# sensor_004.net
KiCad netlist of a schematic drawn in EAGLE
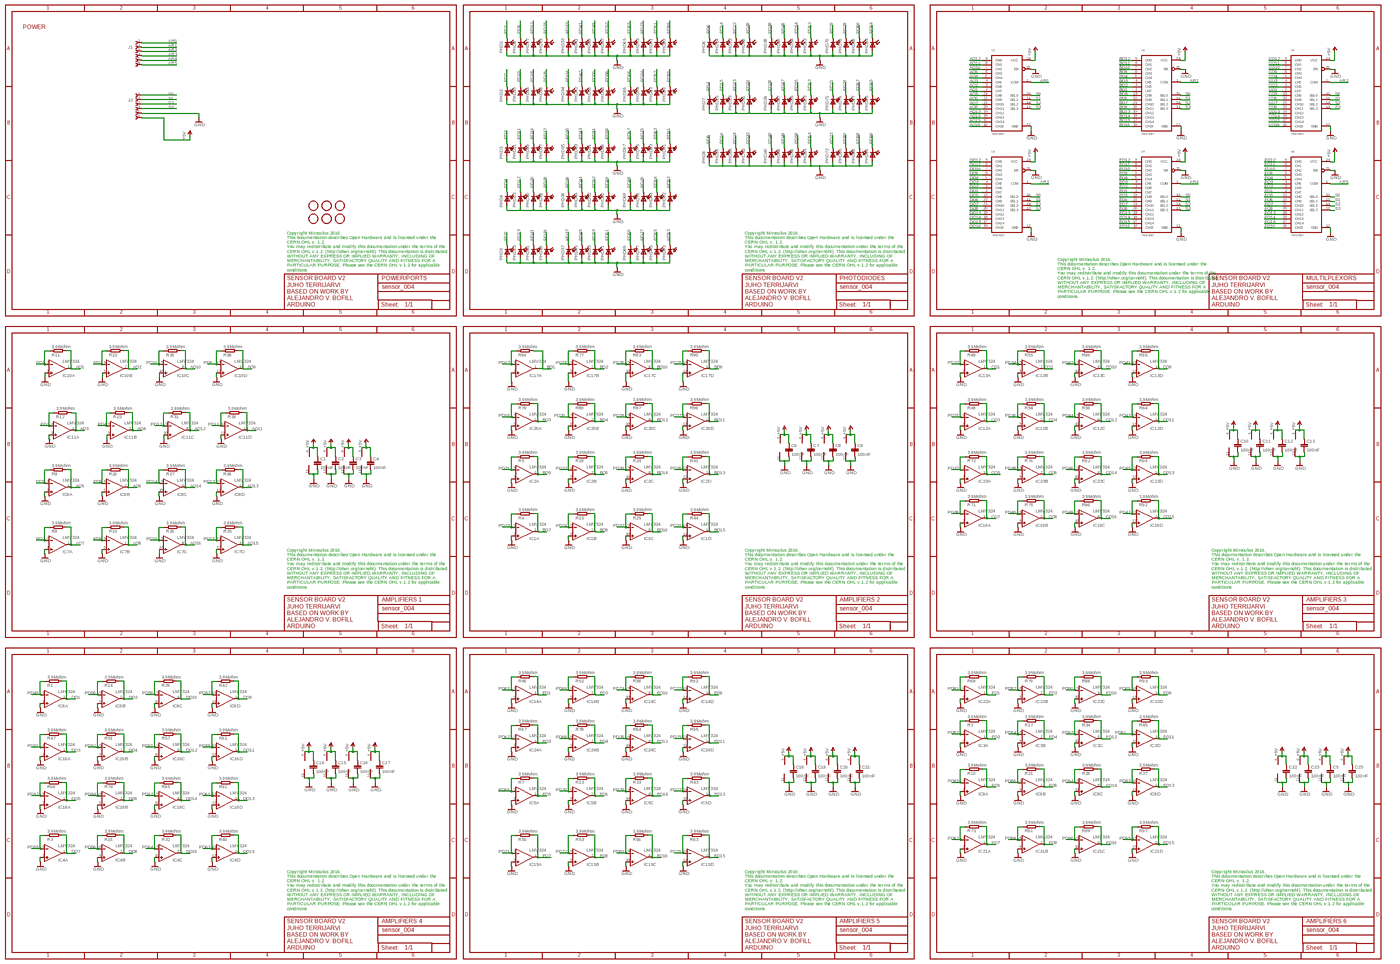
[diagram p0: schematic, sheet 1, overview]
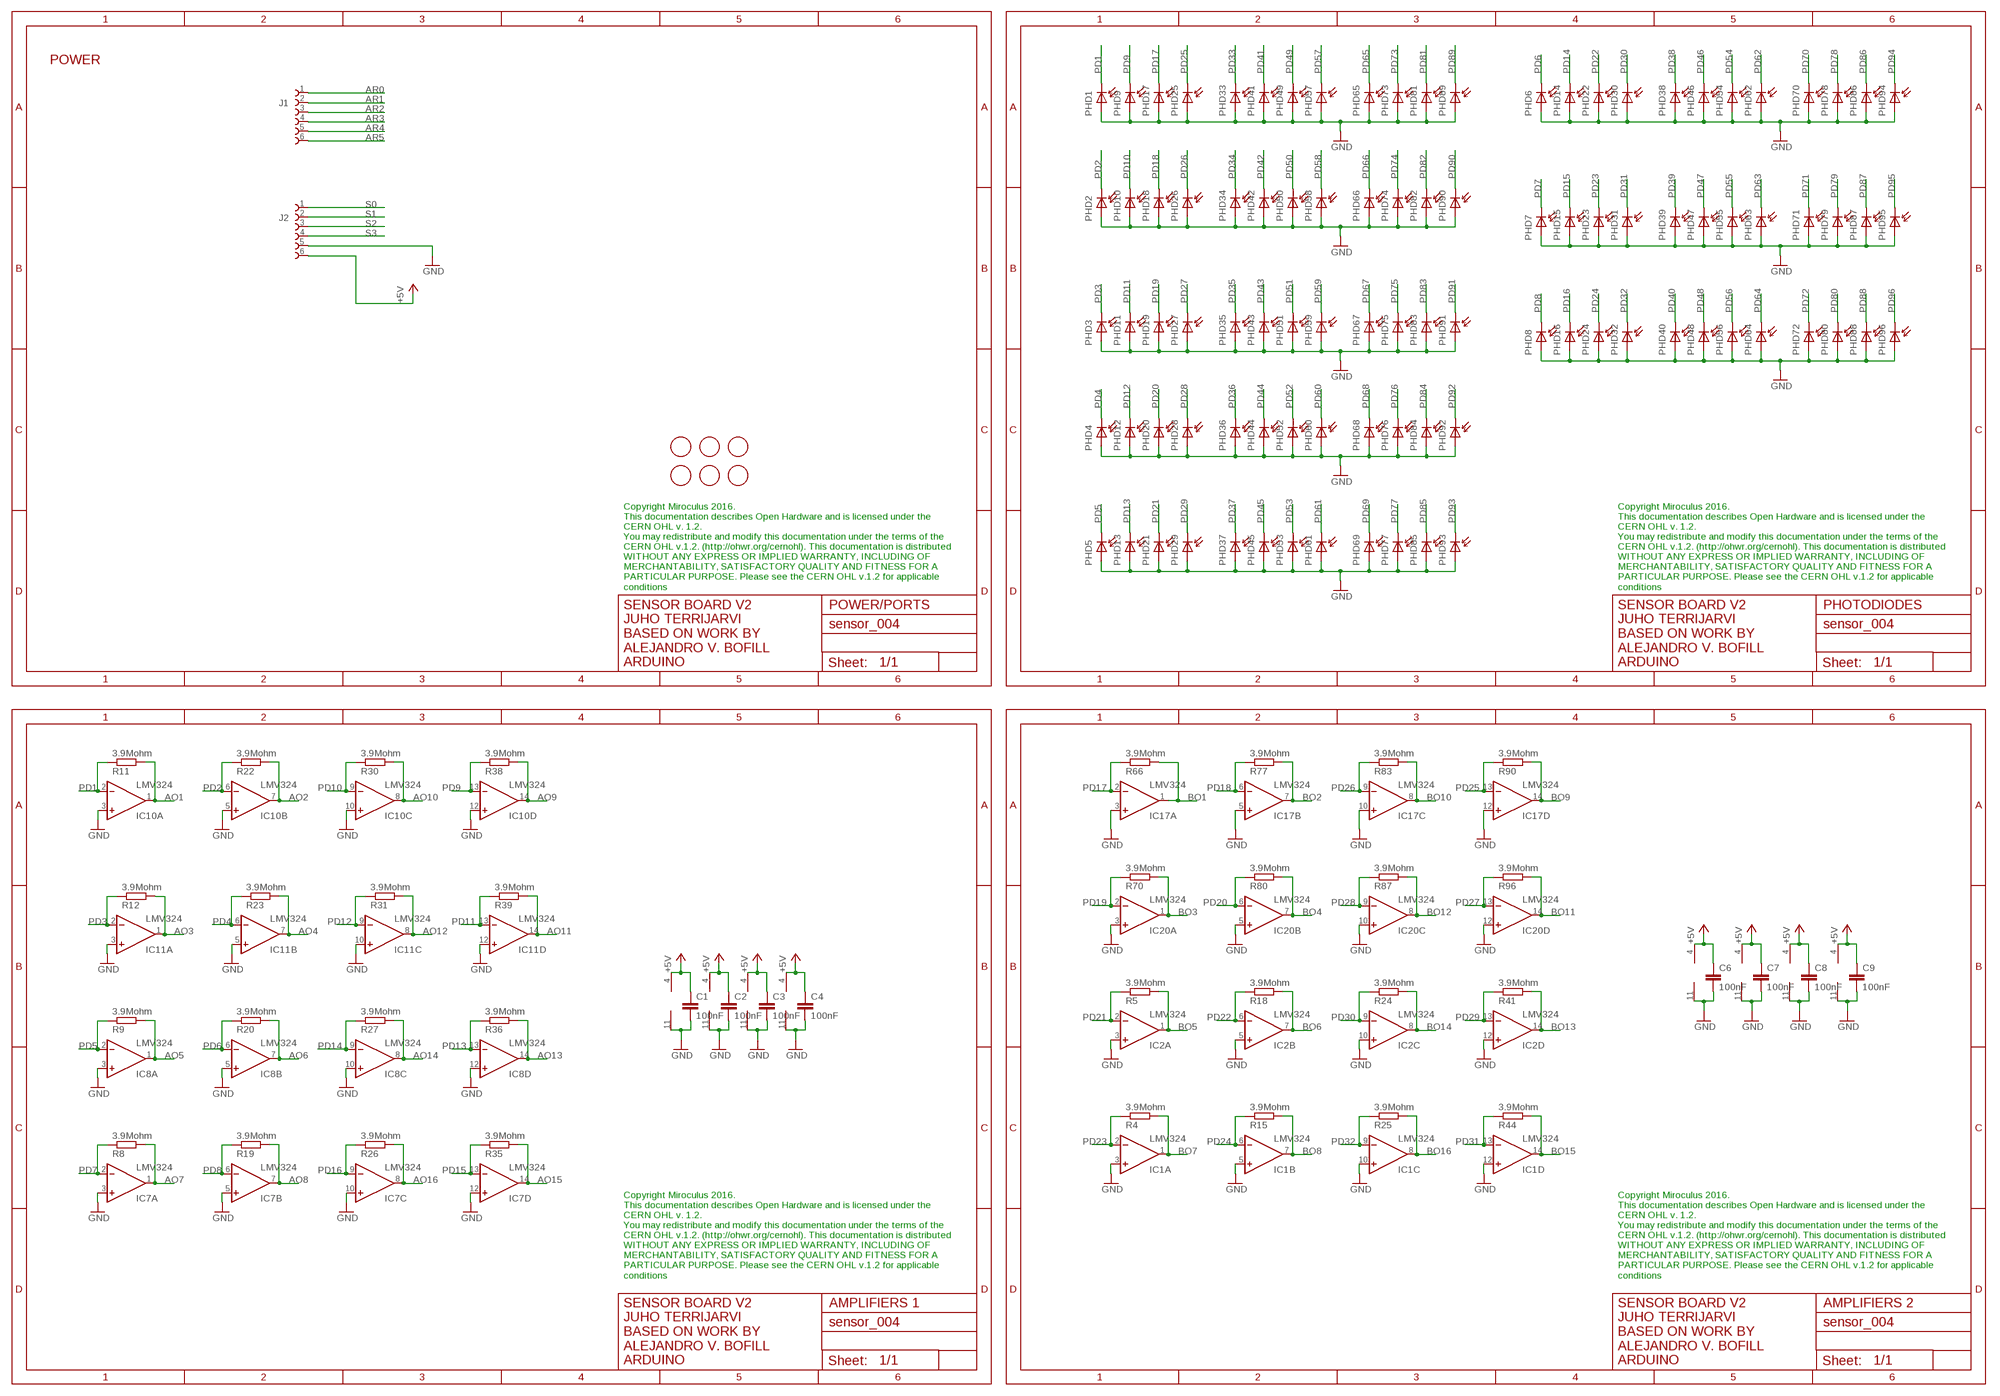
[diagram p1: schematic, sheet 1, part 1 of 4]
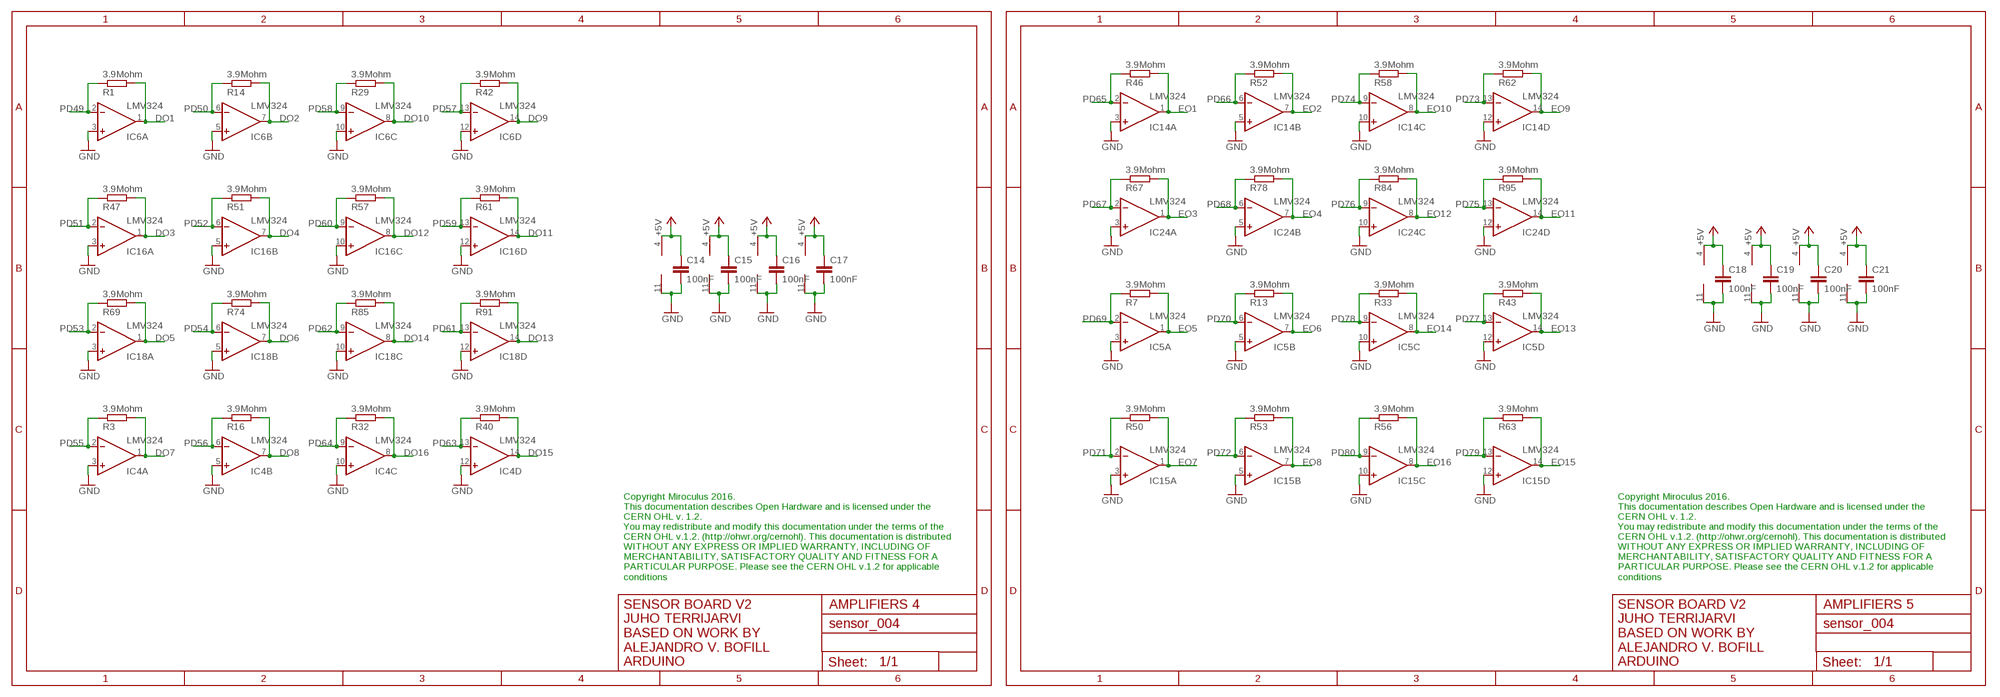
[diagram p2: schematic, sheet 1, part 2 of 4]
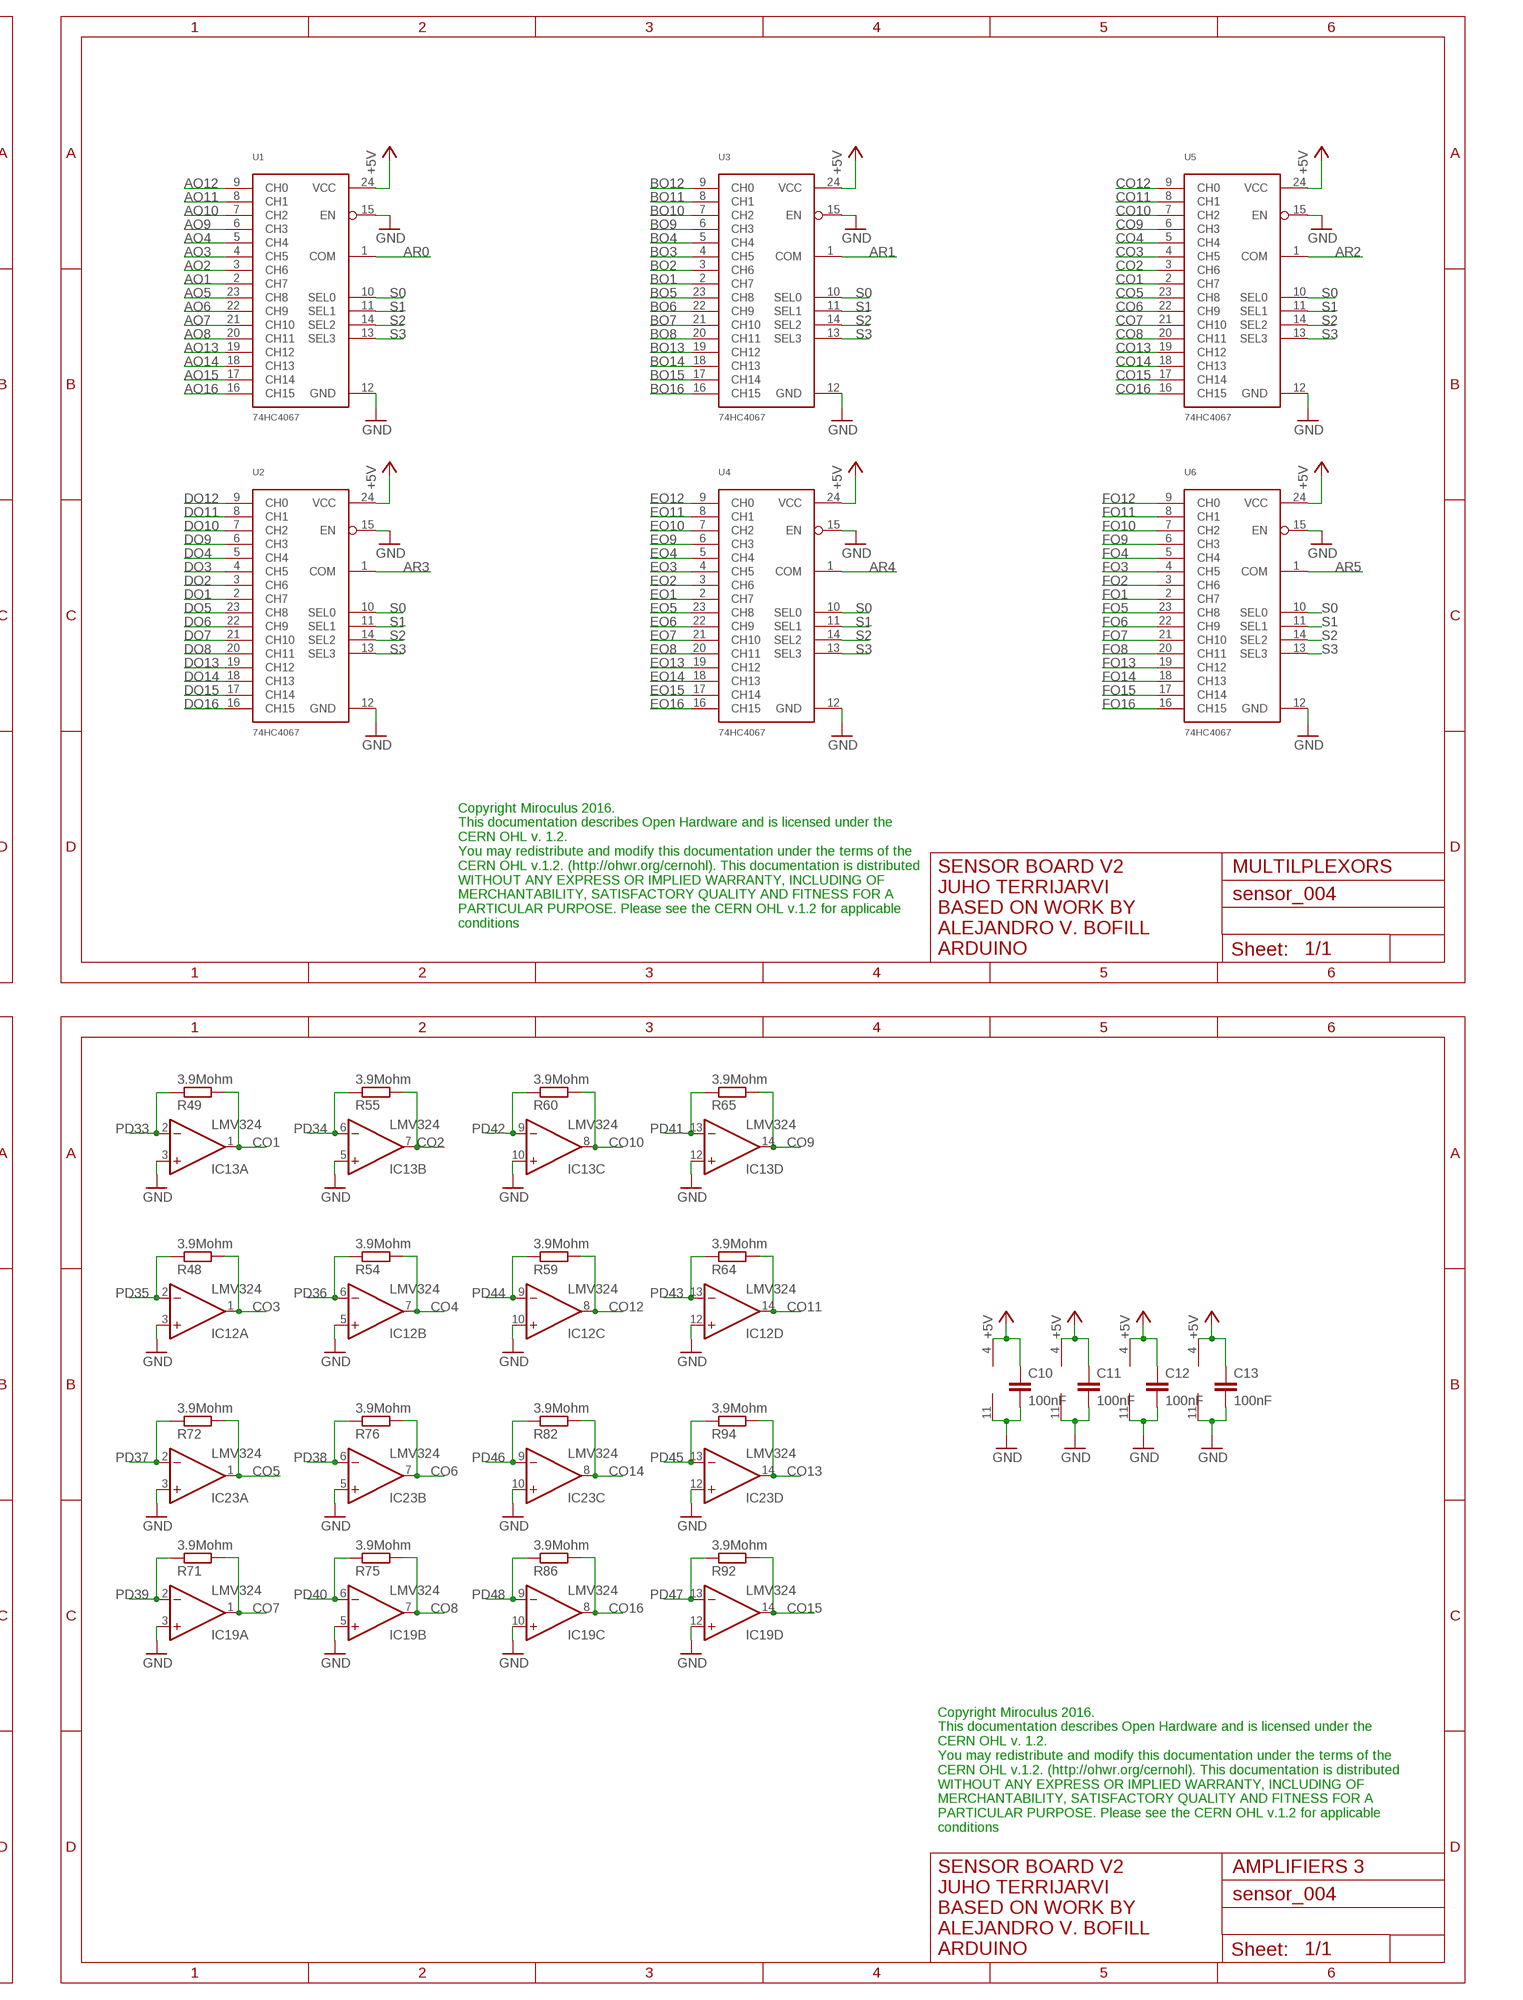
[diagram p3: schematic, sheet 1, part 3 of 4]
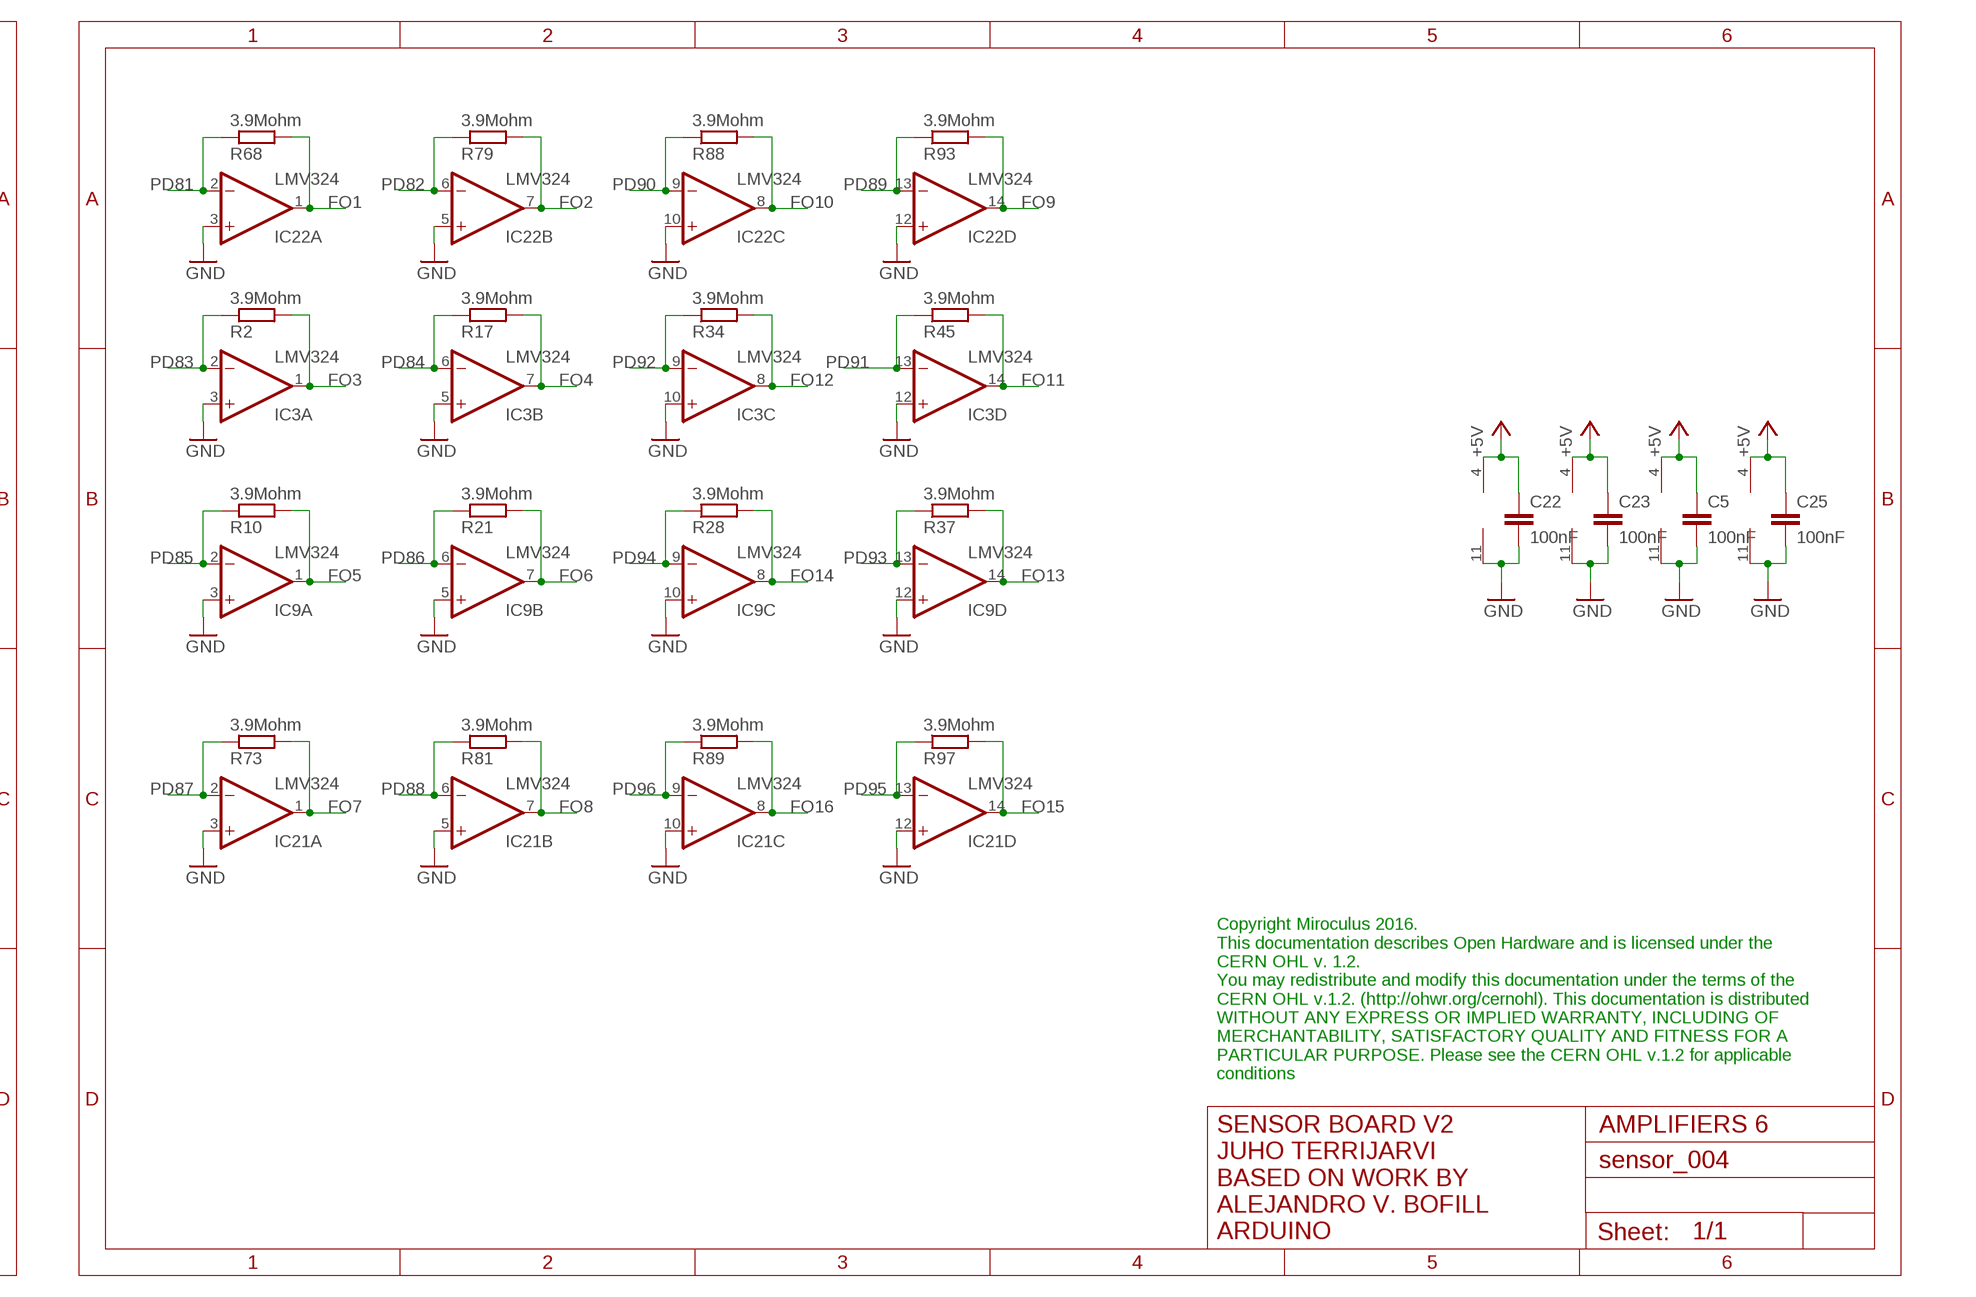
[diagram p4: schematic, sheet 1, part 4 of 4]

(export (version "E")
  (design (tool "Eeschema 10.0.6"))
  (components
    (comp (ref "C1")
      (value "100nF")
      (footprint "eagle-import:C0603")
      (libsource (lib "eagle-import") (part "C-EUC0603"))
    )
    (comp (ref "C2")
      (value "100nF")
      (footprint "eagle-import:C0603")
      (libsource (lib "eagle-import") (part "C-EUC0603"))
    )
    (comp (ref "C3")
      (value "100nF")
      (footprint "eagle-import:C0603")
      (libsource (lib "eagle-import") (part "C-EUC0603"))
    )
    (comp (ref "C4")
      (value "100nF")
      (footprint "eagle-import:C0603")
      (libsource (lib "eagle-import") (part "C-EUC0603"))
    )
    (comp (ref "C5")
      (value "100nF")
      (footprint "eagle-import:C0603")
      (libsource (lib "eagle-import") (part "C-EUC0603"))
    )
    (comp (ref "C6")
      (value "100nF")
      (footprint "eagle-import:C0603")
      (libsource (lib "eagle-import") (part "C-EUC0603"))
    )
    (comp (ref "C7")
      (value "100nF")
      (footprint "eagle-import:C0603")
      (libsource (lib "eagle-import") (part "C-EUC0603"))
    )
    (comp (ref "C8")
      (value "100nF")
      (footprint "eagle-import:C0603")
      (libsource (lib "eagle-import") (part "C-EUC0603"))
    )
    (comp (ref "C9")
      (value "100nF")
      (footprint "eagle-import:C0603")
      (libsource (lib "eagle-import") (part "C-EUC0603"))
    )
    (comp (ref "C10")
      (value "100nF")
      (footprint "eagle-import:C0603")
      (libsource (lib "eagle-import") (part "C-EUC0603"))
    )
    (comp (ref "C11")
      (value "100nF")
      (footprint "eagle-import:C0603")
      (libsource (lib "eagle-import") (part "C-EUC0603"))
    )
    (comp (ref "C12")
      (value "100nF")
      (footprint "eagle-import:C0603")
      (libsource (lib "eagle-import") (part "C-EUC0603"))
    )
    (comp (ref "C13")
      (value "100nF")
      (footprint "eagle-import:C0603")
      (libsource (lib "eagle-import") (part "C-EUC0603"))
    )
    (comp (ref "C14")
      (value "100nF")
      (footprint "eagle-import:C0603")
      (libsource (lib "eagle-import") (part "C-EUC0603"))
    )
    (comp (ref "C15")
      (value "100nF")
      (footprint "eagle-import:C0603")
      (libsource (lib "eagle-import") (part "C-EUC0603"))
    )
    (comp (ref "C16")
      (value "100nF")
      (footprint "eagle-import:C0603")
      (libsource (lib "eagle-import") (part "C-EUC0603"))
    )
    (comp (ref "C17")
      (value "100nF")
      (footprint "eagle-import:C0603")
      (libsource (lib "eagle-import") (part "C-EUC0603"))
    )
    (comp (ref "C18")
      (value "100nF")
      (footprint "eagle-import:C0603")
      (libsource (lib "eagle-import") (part "C-EUC0603"))
    )
    (comp (ref "C19")
      (value "100nF")
      (footprint "eagle-import:C0603")
      (libsource (lib "eagle-import") (part "C-EUC0603"))
    )
    (comp (ref "C20")
      (value "100nF")
      (footprint "eagle-import:C0603")
      (libsource (lib "eagle-import") (part "C-EUC0603"))
    )
    (comp (ref "C21")
      (value "100nF")
      (footprint "eagle-import:C0603")
      (libsource (lib "eagle-import") (part "C-EUC0603"))
    )
    (comp (ref "C22")
      (value "100nF")
      (footprint "eagle-import:C0603")
      (libsource (lib "eagle-import") (part "C-EUC0603"))
    )
    (comp (ref "C23")
      (value "100nF")
      (footprint "eagle-import:C0603")
      (libsource (lib "eagle-import") (part "C-EUC0603"))
    )
    (comp (ref "C25")
      (value "100nF")
      (footprint "eagle-import:C0603")
      (libsource (lib "eagle-import") (part "C-EUC0603"))
    )
    (comp (ref "FD1")
      (value "FIDUCIALMOUNT")
      (footprint "eagle-import:FIDUCIA-MOUNT")
      (libsource (lib "eagle-import") (part "FIDUCIALMOUNT"))
    )
    (comp (ref "FD2")
      (value "FIDUCIALMOUNT")
      (footprint "eagle-import:FIDUCIA-MOUNT")
      (libsource (lib "eagle-import") (part "FIDUCIALMOUNT"))
    )
    (comp (ref "FD3")
      (value "FIDUCIALMOUNT")
      (footprint "eagle-import:FIDUCIA-MOUNT")
      (libsource (lib "eagle-import") (part "FIDUCIALMOUNT"))
    )
    (comp (ref "FD4")
      (value "FIDUCIALMOUNT")
      (footprint "eagle-import:FIDUCIA-MOUNT")
      (libsource (lib "eagle-import") (part "FIDUCIALMOUNT"))
    )
    (comp (ref "FD5")
      (value "FIDUCIALMOUNT")
      (footprint "eagle-import:FIDUCIA-MOUNT")
      (libsource (lib "eagle-import") (part "FIDUCIALMOUNT"))
    )
    (comp (ref "FD6")
      (value "FIDUCIALMOUNT")
      (footprint "eagle-import:FIDUCIA-MOUNT")
      (libsource (lib "eagle-import") (part "FIDUCIALMOUNT"))
    )
    (comp (ref "IC1")
      (value "LMV324")
      (footprint "eagle-import:SO14")
      (libsource (lib "eagle-import") (part "TL074D"))
    )
    (comp (ref "IC2")
      (value "LMV324")
      (footprint "eagle-import:SO14")
      (libsource (lib "eagle-import") (part "TL074D"))
    )
    (comp (ref "IC3")
      (value "LMV324")
      (footprint "eagle-import:SO14")
      (libsource (lib "eagle-import") (part "TL074D"))
    )
    (comp (ref "IC4")
      (value "LMV324")
      (footprint "eagle-import:SO14")
      (libsource (lib "eagle-import") (part "TL074D"))
    )
    (comp (ref "IC5")
      (value "LMV324")
      (footprint "eagle-import:SO14")
      (libsource (lib "eagle-import") (part "TL074D"))
    )
    (comp (ref "IC6")
      (value "LMV324")
      (footprint "eagle-import:SO14")
      (libsource (lib "eagle-import") (part "TL074D"))
    )
    (comp (ref "IC7")
      (value "LMV324")
      (footprint "eagle-import:SO14")
      (libsource (lib "eagle-import") (part "TL074D"))
    )
    (comp (ref "IC8")
      (value "LMV324")
      (footprint "eagle-import:SO14")
      (libsource (lib "eagle-import") (part "TL074D"))
    )
    (comp (ref "IC9")
      (value "LMV324")
      (footprint "eagle-import:SO14")
      (libsource (lib "eagle-import") (part "TL074D"))
    )
    (comp (ref "IC10")
      (value "LMV324")
      (footprint "eagle-import:SO14")
      (libsource (lib "eagle-import") (part "TL074D"))
    )
    (comp (ref "IC11")
      (value "LMV324")
      (footprint "eagle-import:SO14")
      (libsource (lib "eagle-import") (part "TL074D"))
    )
    (comp (ref "IC12")
      (value "LMV324")
      (footprint "eagle-import:SO14")
      (libsource (lib "eagle-import") (part "TL074D"))
    )
    (comp (ref "IC13")
      (value "LMV324")
      (footprint "eagle-import:SO14")
      (libsource (lib "eagle-import") (part "TL074D"))
    )
    (comp (ref "IC14")
      (value "LMV324")
      (footprint "eagle-import:SO14")
      (libsource (lib "eagle-import") (part "TL074D"))
    )
    (comp (ref "IC15")
      (value "LMV324")
      (footprint "eagle-import:SO14")
      (libsource (lib "eagle-import") (part "TL074D"))
    )
    (comp (ref "IC16")
      (value "LMV324")
      (footprint "eagle-import:SO14")
      (libsource (lib "eagle-import") (part "TL074D"))
    )
    (comp (ref "IC17")
      (value "LMV324")
      (footprint "eagle-import:SO14")
      (libsource (lib "eagle-import") (part "TL074D"))
    )
    (comp (ref "IC18")
      (value "LMV324")
      (footprint "eagle-import:SO14")
      (libsource (lib "eagle-import") (part "TL074D"))
    )
    (comp (ref "IC19")
      (value "LMV324")
      (footprint "eagle-import:SO14")
      (libsource (lib "eagle-import") (part "TL074D"))
    )
    (comp (ref "IC20")
      (value "LMV324")
      (footprint "eagle-import:SO14")
      (libsource (lib "eagle-import") (part "TL074D"))
    )
    (comp (ref "IC21")
      (value "LMV324")
      (footprint "eagle-import:SO14")
      (libsource (lib "eagle-import") (part "TL074D"))
    )
    (comp (ref "IC22")
      (value "LMV324")
      (footprint "eagle-import:SO14")
      (libsource (lib "eagle-import") (part "TL074D"))
    )
    (comp (ref "IC23")
      (value "LMV324")
      (footprint "eagle-import:SO14")
      (libsource (lib "eagle-import") (part "TL074D"))
    )
    (comp (ref "IC24")
      (value "LMV324")
      (footprint "eagle-import:SO14")
      (libsource (lib "eagle-import") (part "TL074D"))
    )
    (comp (ref "J1")
      (value "68710614522")
      (footprint "eagle-import:68710614522")
      (libsource (lib "eagle-import") (part "68710614522"))
    )
    (comp (ref "J2")
      (value "68710614522")
      (footprint "eagle-import:68710614522")
      (libsource (lib "eagle-import") (part "68710614522"))
    )
    (comp (ref "PHD1")
      (value "CLS15-22C/L213G/TR8")
      (footprint "eagle-import:PD_2")
      (libsource (lib "eagle-import") (part "PD_2"))
    )
    (comp (ref "PHD2")
      (value "CLS15-22C/L213G/TR8")
      (footprint "eagle-import:PD_2")
      (libsource (lib "eagle-import") (part "PD_2"))
    )
    (comp (ref "PHD3")
      (value "CLS15-22C/L213G/TR8")
      (footprint "eagle-import:PD_2")
      (libsource (lib "eagle-import") (part "PD_2"))
    )
    (comp (ref "PHD4")
      (value "CLS15-22C/L213G/TR8")
      (footprint "eagle-import:PD_2")
      (libsource (lib "eagle-import") (part "PD_2"))
    )
    (comp (ref "PHD5")
      (value "CLS15-22C/L213G/TR8")
      (footprint "eagle-import:PD_2")
      (libsource (lib "eagle-import") (part "PD_2"))
    )
    (comp (ref "PHD6")
      (value "CLS15-22C/L213G/TR8")
      (footprint "eagle-import:PD_2")
      (libsource (lib "eagle-import") (part "PD_2"))
    )
    (comp (ref "PHD7")
      (value "CLS15-22C/L213G/TR8")
      (footprint "eagle-import:PD_2")
      (libsource (lib "eagle-import") (part "PD_2"))
    )
    (comp (ref "PHD8")
      (value "CLS15-22C/L213G/TR8")
      (footprint "eagle-import:PD_2")
      (libsource (lib "eagle-import") (part "PD_2"))
    )
    (comp (ref "PHD9")
      (value "CLS15-22C/L213G/TR8")
      (footprint "eagle-import:PD_2")
      (libsource (lib "eagle-import") (part "PD_2"))
    )
    (comp (ref "PHD10")
      (value "CLS15-22C/L213G/TR8")
      (footprint "eagle-import:PD_2")
      (libsource (lib "eagle-import") (part "PD_2"))
    )
    (comp (ref "PHD11")
      (value "CLS15-22C/L213G/TR8")
      (footprint "eagle-import:PD_2")
      (libsource (lib "eagle-import") (part "PD_2"))
    )
    (comp (ref "PHD12")
      (value "CLS15-22C/L213G/TR8")
      (footprint "eagle-import:PD_2")
      (libsource (lib "eagle-import") (part "PD_2"))
    )
    (comp (ref "PHD13")
      (value "CLS15-22C/L213G/TR8")
      (footprint "eagle-import:PD_2")
      (libsource (lib "eagle-import") (part "PD_2"))
    )
    (comp (ref "PHD14")
      (value "CLS15-22C/L213G/TR8")
      (footprint "eagle-import:PD_2")
      (libsource (lib "eagle-import") (part "PD_2"))
    )
    (comp (ref "PHD15")
      (value "CLS15-22C/L213G/TR8")
      (footprint "eagle-import:PD_2")
      (libsource (lib "eagle-import") (part "PD_2"))
    )
    (comp (ref "PHD16")
      (value "CLS15-22C/L213G/TR8")
      (footprint "eagle-import:PD_2")
      (libsource (lib "eagle-import") (part "PD_2"))
    )
    (comp (ref "PHD17")
      (value "CLS15-22C/L213G/TR8")
      (footprint "eagle-import:PD_2")
      (libsource (lib "eagle-import") (part "PD_2"))
    )
    (comp (ref "PHD18")
      (value "CLS15-22C/L213G/TR8")
      (footprint "eagle-import:PD_2")
      (libsource (lib "eagle-import") (part "PD_2"))
    )
    (comp (ref "PHD19")
      (value "CLS15-22C/L213G/TR8")
      (footprint "eagle-import:PD_2")
      (libsource (lib "eagle-import") (part "PD_2"))
    )
    (comp (ref "PHD20")
      (value "CLS15-22C/L213G/TR8")
      (footprint "eagle-import:PD_2")
      (libsource (lib "eagle-import") (part "PD_2"))
    )
    (comp (ref "PHD21")
      (value "CLS15-22C/L213G/TR8")
      (footprint "eagle-import:PD_2")
      (libsource (lib "eagle-import") (part "PD_2"))
    )
    (comp (ref "PHD22")
      (value "CLS15-22C/L213G/TR8")
      (footprint "eagle-import:PD_2")
      (libsource (lib "eagle-import") (part "PD_2"))
    )
    (comp (ref "PHD23")
      (value "CLS15-22C/L213G/TR8")
      (footprint "eagle-import:PD_2")
      (libsource (lib "eagle-import") (part "PD_2"))
    )
    (comp (ref "PHD24")
      (value "CLS15-22C/L213G/TR8")
      (footprint "eagle-import:PD_2")
      (libsource (lib "eagle-import") (part "PD_2"))
    )
    (comp (ref "PHD25")
      (value "CLS15-22C/L213G/TR8")
      (footprint "eagle-import:PD_2")
      (libsource (lib "eagle-import") (part "PD_2"))
    )
    (comp (ref "PHD26")
      (value "CLS15-22C/L213G/TR8")
      (footprint "eagle-import:PD_2")
      (libsource (lib "eagle-import") (part "PD_2"))
    )
    (comp (ref "PHD27")
      (value "CLS15-22C/L213G/TR8")
      (footprint "eagle-import:PD_2")
      (libsource (lib "eagle-import") (part "PD_2"))
    )
    (comp (ref "PHD28")
      (value "CLS15-22C/L213G/TR8")
      (footprint "eagle-import:PD_2")
      (libsource (lib "eagle-import") (part "PD_2"))
    )
    (comp (ref "PHD29")
      (value "CLS15-22C/L213G/TR8")
      (footprint "eagle-import:PD_2")
      (libsource (lib "eagle-import") (part "PD_2"))
    )
    (comp (ref "PHD30")
      (value "CLS15-22C/L213G/TR8")
      (footprint "eagle-import:PD_2")
      (libsource (lib "eagle-import") (part "PD_2"))
    )
    (comp (ref "PHD31")
      (value "CLS15-22C/L213G/TR8")
      (footprint "eagle-import:PD_2")
      (libsource (lib "eagle-import") (part "PD_2"))
    )
    (comp (ref "PHD32")
      (value "CLS15-22C/L213G/TR8")
      (footprint "eagle-import:PD_2")
      (libsource (lib "eagle-import") (part "PD_2"))
    )
    (comp (ref "PHD33")
      (value "CLS15-22C/L213G/TR8")
      (footprint "eagle-import:PD_2")
      (libsource (lib "eagle-import") (part "PD_2"))
    )
    (comp (ref "PHD34")
      (value "CLS15-22C/L213G/TR8")
      (footprint "eagle-import:PD_2")
      (libsource (lib "eagle-import") (part "PD_2"))
    )
    (comp (ref "PHD35")
      (value "CLS15-22C/L213G/TR8")
      (footprint "eagle-import:PD_2")
      (libsource (lib "eagle-import") (part "PD_2"))
    )
    (comp (ref "PHD36")
      (value "CLS15-22C/L213G/TR8")
      (footprint "eagle-import:PD_2")
      (libsource (lib "eagle-import") (part "PD_2"))
    )
    (comp (ref "PHD37")
      (value "CLS15-22C/L213G/TR8")
      (footprint "eagle-import:PD_2")
      (libsource (lib "eagle-import") (part "PD_2"))
    )
    (comp (ref "PHD38")
      (value "CLS15-22C/L213G/TR8")
      (footprint "eagle-import:PD_2")
      (libsource (lib "eagle-import") (part "PD_2"))
    )
    (comp (ref "PHD39")
      (value "CLS15-22C/L213G/TR8")
      (footprint "eagle-import:PD_2")
      (libsource (lib "eagle-import") (part "PD_2"))
    )
    (comp (ref "PHD40")
      (value "CLS15-22C/L213G/TR8")
      (footprint "eagle-import:PD_2")
      (libsource (lib "eagle-import") (part "PD_2"))
    )
    (comp (ref "PHD41")
      (value "CLS15-22C/L213G/TR8")
      (footprint "eagle-import:PD_2")
      (libsource (lib "eagle-import") (part "PD_2"))
    )
    (comp (ref "PHD42")
      (value "CLS15-22C/L213G/TR8")
      (footprint "eagle-import:PD_2")
      (libsource (lib "eagle-import") (part "PD_2"))
    )
    (comp (ref "PHD43")
      (value "CLS15-22C/L213G/TR8")
      (footprint "eagle-import:PD_2")
      (libsource (lib "eagle-import") (part "PD_2"))
    )
    (comp (ref "PHD44")
      (value "CLS15-22C/L213G/TR8")
      (footprint "eagle-import:PD_2")
      (libsource (lib "eagle-import") (part "PD_2"))
    )
    (comp (ref "PHD45")
      (value "CLS15-22C/L213G/TR8")
      (footprint "eagle-import:PD_2")
      (libsource (lib "eagle-import") (part "PD_2"))
    )
    (comp (ref "PHD46")
      (value "CLS15-22C/L213G/TR8")
      (footprint "eagle-import:PD_2")
      (libsource (lib "eagle-import") (part "PD_2"))
    )
    (comp (ref "PHD47")
      (value "CLS15-22C/L213G/TR8")
      (footprint "eagle-import:PD_2")
      (libsource (lib "eagle-import") (part "PD_2"))
    )
    (comp (ref "PHD48")
      (value "CLS15-22C/L213G/TR8")
      (footprint "eagle-import:PD_2")
      (libsource (lib "eagle-import") (part "PD_2"))
    )
    (comp (ref "PHD49")
      (value "CLS15-22C/L213G/TR8")
      (footprint "eagle-import:PD_2")
      (libsource (lib "eagle-import") (part "PD_2"))
    )
    (comp (ref "PHD50")
      (value "CLS15-22C/L213G/TR8")
      (footprint "eagle-import:PD_2")
      (libsource (lib "eagle-import") (part "PD_2"))
    )
    (comp (ref "PHD51")
      (value "CLS15-22C/L213G/TR8")
      (footprint "eagle-import:PD_2")
      (libsource (lib "eagle-import") (part "PD_2"))
    )
    (comp (ref "PHD52")
      (value "CLS15-22C/L213G/TR8")
      (footprint "eagle-import:PD_2")
      (libsource (lib "eagle-import") (part "PD_2"))
    )
    (comp (ref "PHD53")
      (value "CLS15-22C/L213G/TR8")
      (footprint "eagle-import:PD_2")
      (libsource (lib "eagle-import") (part "PD_2"))
    )
    (comp (ref "PHD54")
      (value "CLS15-22C/L213G/TR8")
      (footprint "eagle-import:PD_2")
      (libsource (lib "eagle-import") (part "PD_2"))
    )
    (comp (ref "PHD55")
      (value "CLS15-22C/L213G/TR8")
      (footprint "eagle-import:PD_2")
      (libsource (lib "eagle-import") (part "PD_2"))
    )
    (comp (ref "PHD56")
      (value "CLS15-22C/L213G/TR8")
      (footprint "eagle-import:PD_2")
      (libsource (lib "eagle-import") (part "PD_2"))
    )
    (comp (ref "PHD57")
      (value "CLS15-22C/L213G/TR8")
      (footprint "eagle-import:PD_2")
      (libsource (lib "eagle-import") (part "PD_2"))
    )
    (comp (ref "PHD58")
      (value "CLS15-22C/L213G/TR8")
      (footprint "eagle-import:PD_2")
      (libsource (lib "eagle-import") (part "PD_2"))
    )
    (comp (ref "PHD59")
      (value "CLS15-22C/L213G/TR8")
      (footprint "eagle-import:PD_2")
      (libsource (lib "eagle-import") (part "PD_2"))
    )
    (comp (ref "PHD60")
      (value "CLS15-22C/L213G/TR8")
      (footprint "eagle-import:PD_2")
      (libsource (lib "eagle-import") (part "PD_2"))
    )
    (comp (ref "PHD61")
      (value "CLS15-22C/L213G/TR8")
      (footprint "eagle-import:PD_2")
      (libsource (lib "eagle-import") (part "PD_2"))
    )
    (comp (ref "PHD62")
      (value "CLS15-22C/L213G/TR8")
      (footprint "eagle-import:PD_2")
      (libsource (lib "eagle-import") (part "PD_2"))
    )
    (comp (ref "PHD63")
      (value "CLS15-22C/L213G/TR8")
      (footprint "eagle-import:PD_2")
      (libsource (lib "eagle-import") (part "PD_2"))
    )
    (comp (ref "PHD64")
      (value "CLS15-22C/L213G/TR8")
      (footprint "eagle-import:PD_2")
      (libsource (lib "eagle-import") (part "PD_2"))
    )
    (comp (ref "PHD65")
      (value "CLS15-22C/L213G/TR8")
      (footprint "eagle-import:PD_2")
      (libsource (lib "eagle-import") (part "PD_2"))
    )
    (comp (ref "PHD66")
      (value "CLS15-22C/L213G/TR8")
      (footprint "eagle-import:PD_2")
      (libsource (lib "eagle-import") (part "PD_2"))
    )
    (comp (ref "PHD67")
      (value "CLS15-22C/L213G/TR8")
      (footprint "eagle-import:PD_2")
      (libsource (lib "eagle-import") (part "PD_2"))
    )
    (comp (ref "PHD68")
      (value "CLS15-22C/L213G/TR8")
      (footprint "eagle-import:PD_2")
      (libsource (lib "eagle-import") (part "PD_2"))
    )
    (comp (ref "PHD69")
      (value "CLS15-22C/L213G/TR8")
      (footprint "eagle-import:PD_2")
      (libsource (lib "eagle-import") (part "PD_2"))
    )
    (comp (ref "PHD70")
      (value "CLS15-22C/L213G/TR8")
      (footprint "eagle-import:PD_2")
      (libsource (lib "eagle-import") (part "PD_2"))
    )
    (comp (ref "PHD71")
      (value "CLS15-22C/L213G/TR8")
      (footprint "eagle-import:PD_2")
      (libsource (lib "eagle-import") (part "PD_2"))
    )
    (comp (ref "PHD72")
      (value "CLS15-22C/L213G/TR8")
      (footprint "eagle-import:PD_2")
      (libsource (lib "eagle-import") (part "PD_2"))
    )
    (comp (ref "PHD73")
      (value "CLS15-22C/L213G/TR8")
      (footprint "eagle-import:PD_2")
      (libsource (lib "eagle-import") (part "PD_2"))
    )
    (comp (ref "PHD74")
      (value "CLS15-22C/L213G/TR8")
      (footprint "eagle-import:PD_2")
      (libsource (lib "eagle-import") (part "PD_2"))
    )
    (comp (ref "PHD75")
      (value "CLS15-22C/L213G/TR8")
      (footprint "eagle-import:PD_2")
      (libsource (lib "eagle-import") (part "PD_2"))
    )
    (comp (ref "PHD76")
      (value "CLS15-22C/L213G/TR8")
      (footprint "eagle-import:PD_2")
      (libsource (lib "eagle-import") (part "PD_2"))
    )
    (comp (ref "PHD77")
      (value "CLS15-22C/L213G/TR8")
      (footprint "eagle-import:PD_2")
      (libsource (lib "eagle-import") (part "PD_2"))
    )
    (comp (ref "PHD78")
      (value "CLS15-22C/L213G/TR8")
      (footprint "eagle-import:PD_2")
      (libsource (lib "eagle-import") (part "PD_2"))
    )
    (comp (ref "PHD79")
      (value "CLS15-22C/L213G/TR8")
      (footprint "eagle-import:PD_2")
      (libsource (lib "eagle-import") (part "PD_2"))
    )
    (comp (ref "PHD80")
      (value "CLS15-22C/L213G/TR8")
      (footprint "eagle-import:PD_2")
      (libsource (lib "eagle-import") (part "PD_2"))
    )
    (comp (ref "PHD81")
      (value "CLS15-22C/L213G/TR8")
      (footprint "eagle-import:PD_2")
      (libsource (lib "eagle-import") (part "PD_2"))
    )
    (comp (ref "PHD82")
      (value "CLS15-22C/L213G/TR8")
      (footprint "eagle-import:PD_2")
      (libsource (lib "eagle-import") (part "PD_2"))
    )
    (comp (ref "PHD83")
      (value "CLS15-22C/L213G/TR8")
      (footprint "eagle-import:PD_2")
      (libsource (lib "eagle-import") (part "PD_2"))
    )
    (comp (ref "PHD84")
      (value "CLS15-22C/L213G/TR8")
      (footprint "eagle-import:PD_2")
      (libsource (lib "eagle-import") (part "PD_2"))
    )
    (comp (ref "PHD85")
      (value "CLS15-22C/L213G/TR8")
      (footprint "eagle-import:PD_2")
      (libsource (lib "eagle-import") (part "PD_2"))
    )
    (comp (ref "PHD86")
      (value "CLS15-22C/L213G/TR8")
      (footprint "eagle-import:PD_2")
      (libsource (lib "eagle-import") (part "PD_2"))
    )
    (comp (ref "PHD87")
      (value "CLS15-22C/L213G/TR8")
      (footprint "eagle-import:PD_2")
      (libsource (lib "eagle-import") (part "PD_2"))
    )
    (comp (ref "PHD88")
      (value "CLS15-22C/L213G/TR8")
      (footprint "eagle-import:PD_2")
      (libsource (lib "eagle-import") (part "PD_2"))
    )
    (comp (ref "PHD89")
      (value "CLS15-22C/L213G/TR8")
      (footprint "eagle-import:PD_2")
      (libsource (lib "eagle-import") (part "PD_2"))
    )
    (comp (ref "PHD90")
      (value "CLS15-22C/L213G/TR8")
      (footprint "eagle-import:PD_2")
      (libsource (lib "eagle-import") (part "PD_2"))
    )
    (comp (ref "PHD91")
      (value "CLS15-22C/L213G/TR8")
      (footprint "eagle-import:PD_2")
      (libsource (lib "eagle-import") (part "PD_2"))
    )
    (comp (ref "PHD92")
      (value "CLS15-22C/L213G/TR8")
      (footprint "eagle-import:PD_2")
      (libsource (lib "eagle-import") (part "PD_2"))
    )
    (comp (ref "PHD93")
      (value "CLS15-22C/L213G/TR8")
      (footprint "eagle-import:PD_2")
      (libsource (lib "eagle-import") (part "PD_2"))
    )
    (comp (ref "PHD94")
      (value "CLS15-22C/L213G/TR8")
      (footprint "eagle-import:PD_2")
      (libsource (lib "eagle-import") (part "PD_2"))
    )
    (comp (ref "PHD95")
      (value "CLS15-22C/L213G/TR8")
      (footprint "eagle-import:PD_2")
      (libsource (lib "eagle-import") (part "PD_2"))
    )
    (comp (ref "PHD96")
      (value "CLS15-22C/L213G/TR8")
      (footprint "eagle-import:PD_2")
      (libsource (lib "eagle-import") (part "PD_2"))
    )
    (comp (ref "R1")
      (value "3.9Mohm")
      (footprint "eagle-import:R0603")
      (libsource (lib "eagle-import") (part "R-EU_R0603"))
    )
    (comp (ref "R2")
      (value "3.9Mohm")
      (footprint "eagle-import:R0603")
      (libsource (lib "eagle-import") (part "R-EU_R0603"))
    )
    (comp (ref "R3")
      (value "3.9Mohm")
      (footprint "eagle-import:R0603")
      (libsource (lib "eagle-import") (part "R-EU_R0603"))
    )
    (comp (ref "R4")
      (value "3.9Mohm")
      (footprint "eagle-import:R0603")
      (libsource (lib "eagle-import") (part "R-EU_R0603"))
    )
    (comp (ref "R5")
      (value "3.9Mohm")
      (footprint "eagle-import:R0603")
      (libsource (lib "eagle-import") (part "R-EU_R0603"))
    )
    (comp (ref "R7")
      (value "3.9Mohm")
      (footprint "eagle-import:R0603")
      (libsource (lib "eagle-import") (part "R-EU_R0603"))
    )
    (comp (ref "R8")
      (value "3.9Mohm")
      (footprint "eagle-import:R0603")
      (libsource (lib "eagle-import") (part "R-EU_R0603"))
    )
    (comp (ref "R9")
      (value "3.9Mohm")
      (footprint "eagle-import:R0603")
      (libsource (lib "eagle-import") (part "R-EU_R0603"))
    )
    (comp (ref "R10")
      (value "3.9Mohm")
      (footprint "eagle-import:R0603")
      (libsource (lib "eagle-import") (part "R-EU_R0603"))
    )
    (comp (ref "R11")
      (value "3.9Mohm")
      (footprint "eagle-import:R0603")
      (libsource (lib "eagle-import") (part "R-EU_R0603"))
    )
    (comp (ref "R12")
      (value "3.9Mohm")
      (footprint "eagle-import:R0603")
      (libsource (lib "eagle-import") (part "R-EU_R0603"))
    )
    (comp (ref "R13")
      (value "3.9Mohm")
      (footprint "eagle-import:R0603")
      (libsource (lib "eagle-import") (part "R-EU_R0603"))
    )
    (comp (ref "R14")
      (value "3.9Mohm")
      (footprint "eagle-import:R0603")
      (libsource (lib "eagle-import") (part "R-EU_R0603"))
    )
    (comp (ref "R15")
      (value "3.9Mohm")
      (footprint "eagle-import:R0603")
      (libsource (lib "eagle-import") (part "R-EU_R0603"))
    )
    (comp (ref "R16")
      (value "3.9Mohm")
      (footprint "eagle-import:R0603")
      (libsource (lib "eagle-import") (part "R-EU_R0603"))
    )
    (comp (ref "R17")
      (value "3.9Mohm")
      (footprint "eagle-import:R0603")
      (libsource (lib "eagle-import") (part "R-EU_R0603"))
    )
    (comp (ref "R18")
      (value "3.9Mohm")
      (footprint "eagle-import:R0603")
      (libsource (lib "eagle-import") (part "R-EU_R0603"))
    )
    (comp (ref "R19")
      (value "3.9Mohm")
      (footprint "eagle-import:R0603")
      (libsource (lib "eagle-import") (part "R-EU_R0603"))
    )
    (comp (ref "R20")
      (value "3.9Mohm")
      (footprint "eagle-import:R0603")
      (libsource (lib "eagle-import") (part "R-EU_R0603"))
    )
    (comp (ref "R21")
      (value "3.9Mohm")
      (footprint "eagle-import:R0603")
      (libsource (lib "eagle-import") (part "R-EU_R0603"))
    )
    (comp (ref "R22")
      (value "3.9Mohm")
      (footprint "eagle-import:R0603")
      (libsource (lib "eagle-import") (part "R-EU_R0603"))
    )
    (comp (ref "R23")
      (value "3.9Mohm")
      (footprint "eagle-import:R0603")
      (libsource (lib "eagle-import") (part "R-EU_R0603"))
    )
    (comp (ref "R24")
      (value "3.9Mohm")
      (footprint "eagle-import:R0603")
      (libsource (lib "eagle-import") (part "R-EU_R0603"))
    )
    (comp (ref "R25")
      (value "3.9Mohm")
      (footprint "eagle-import:R0603")
      (libsource (lib "eagle-import") (part "R-EU_R0603"))
    )
    (comp (ref "R26")
      (value "3.9Mohm")
      (footprint "eagle-import:R0603")
      (libsource (lib "eagle-import") (part "R-EU_R0603"))
    )
    (comp (ref "R27")
      (value "3.9Mohm")
      (footprint "eagle-import:R0603")
      (libsource (lib "eagle-import") (part "R-EU_R0603"))
    )
    (comp (ref "R28")
      (value "3.9Mohm")
      (footprint "eagle-import:R0603")
      (libsource (lib "eagle-import") (part "R-EU_R0603"))
    )
    (comp (ref "R29")
      (value "3.9Mohm")
      (footprint "eagle-import:R0603")
      (libsource (lib "eagle-import") (part "R-EU_R0603"))
    )
    (comp (ref "R30")
      (value "3.9Mohm")
      (footprint "eagle-import:R0603")
      (libsource (lib "eagle-import") (part "R-EU_R0603"))
    )
    (comp (ref "R31")
      (value "3.9Mohm")
      (footprint "eagle-import:R0603")
      (libsource (lib "eagle-import") (part "R-EU_R0603"))
    )
    (comp (ref "R32")
      (value "3.9Mohm")
      (footprint "eagle-import:R0603")
      (libsource (lib "eagle-import") (part "R-EU_R0603"))
    )
    (comp (ref "R33")
      (value "3.9Mohm")
      (footprint "eagle-import:R0603")
      (libsource (lib "eagle-import") (part "R-EU_R0603"))
    )
    (comp (ref "R34")
      (value "3.9Mohm")
      (footprint "eagle-import:R0603")
      (libsource (lib "eagle-import") (part "R-EU_R0603"))
    )
    (comp (ref "R35")
      (value "3.9Mohm")
      (footprint "eagle-import:R0603")
      (libsource (lib "eagle-import") (part "R-EU_R0603"))
    )
    (comp (ref "R36")
      (value "3.9Mohm")
      (footprint "eagle-import:R0603")
      (libsource (lib "eagle-import") (part "R-EU_R0603"))
    )
    (comp (ref "R37")
      (value "3.9Mohm")
      (footprint "eagle-import:R0603")
      (libsource (lib "eagle-import") (part "R-EU_R0603"))
    )
    (comp (ref "R38")
      (value "3.9Mohm")
      (footprint "eagle-import:R0603")
      (libsource (lib "eagle-import") (part "R-EU_R0603"))
    )
    (comp (ref "R39")
      (value "3.9Mohm")
      (footprint "eagle-import:R0603")
      (libsource (lib "eagle-import") (part "R-EU_R0603"))
    )
    (comp (ref "R40")
      (value "3.9Mohm")
      (footprint "eagle-import:R0603")
      (libsource (lib "eagle-import") (part "R-EU_R0603"))
    )
    (comp (ref "R41")
      (value "3.9Mohm")
      (footprint "eagle-import:R0603")
      (libsource (lib "eagle-import") (part "R-EU_R0603"))
    )
    (comp (ref "R42")
      (value "3.9Mohm")
      (footprint "eagle-import:R0603")
      (libsource (lib "eagle-import") (part "R-EU_R0603"))
    )
    (comp (ref "R43")
      (value "3.9Mohm")
      (footprint "eagle-import:R0603")
      (libsource (lib "eagle-import") (part "R-EU_R0603"))
    )
    (comp (ref "R44")
      (value "3.9Mohm")
      (footprint "eagle-import:R0603")
      (libsource (lib "eagle-import") (part "R-EU_R0603"))
    )
    (comp (ref "R45")
      (value "3.9Mohm")
      (footprint "eagle-import:R0603")
      (libsource (lib "eagle-import") (part "R-EU_R0603"))
    )
    (comp (ref "R46")
      (value "3.9Mohm")
      (footprint "eagle-import:R0603")
      (libsource (lib "eagle-import") (part "R-EU_R0603"))
    )
    (comp (ref "R47")
      (value "3.9Mohm")
      (footprint "eagle-import:R0603")
      (libsource (lib "eagle-import") (part "R-EU_R0603"))
    )
    (comp (ref "R48")
      (value "3.9Mohm")
      (footprint "eagle-import:R0603")
      (libsource (lib "eagle-import") (part "R-EU_R0603"))
    )
    (comp (ref "R49")
      (value "3.9Mohm")
      (footprint "eagle-import:R0603")
      (libsource (lib "eagle-import") (part "R-EU_R0603"))
    )
    (comp (ref "R50")
      (value "3.9Mohm")
      (footprint "eagle-import:R0603")
      (libsource (lib "eagle-import") (part "R-EU_R0603"))
    )
    (comp (ref "R51")
      (value "3.9Mohm")
      (footprint "eagle-import:R0603")
      (libsource (lib "eagle-import") (part "R-EU_R0603"))
    )
    (comp (ref "R52")
      (value "3.9Mohm")
      (footprint "eagle-import:R0603")
      (libsource (lib "eagle-import") (part "R-EU_R0603"))
    )
    (comp (ref "R53")
      (value "3.9Mohm")
      (footprint "eagle-import:R0603")
      (libsource (lib "eagle-import") (part "R-EU_R0603"))
    )
    (comp (ref "R54")
      (value "3.9Mohm")
      (footprint "eagle-import:R0603")
      (libsource (lib "eagle-import") (part "R-EU_R0603"))
    )
    (comp (ref "R55")
      (value "3.9Mohm")
      (footprint "eagle-import:R0603")
      (libsource (lib "eagle-import") (part "R-EU_R0603"))
    )
    (comp (ref "R56")
      (value "3.9Mohm")
      (footprint "eagle-import:R0603")
      (libsource (lib "eagle-import") (part "R-EU_R0603"))
    )
    (comp (ref "R57")
      (value "3.9Mohm")
      (footprint "eagle-import:R0603")
      (libsource (lib "eagle-import") (part "R-EU_R0603"))
    )
    (comp (ref "R58")
      (value "3.9Mohm")
      (footprint "eagle-import:R0603")
      (libsource (lib "eagle-import") (part "R-EU_R0603"))
    )
    (comp (ref "R59")
      (value "3.9Mohm")
      (footprint "eagle-import:R0603")
      (libsource (lib "eagle-import") (part "R-EU_R0603"))
    )
    (comp (ref "R60")
      (value "3.9Mohm")
      (footprint "eagle-import:R0603")
      (libsource (lib "eagle-import") (part "R-EU_R0603"))
    )
    (comp (ref "R61")
      (value "3.9Mohm")
      (footprint "eagle-import:R0603")
      (libsource (lib "eagle-import") (part "R-EU_R0603"))
    )
    (comp (ref "R62")
      (value "3.9Mohm")
      (footprint "eagle-import:R0603")
      (libsource (lib "eagle-import") (part "R-EU_R0603"))
    )
    (comp (ref "R63")
      (value "3.9Mohm")
      (footprint "eagle-import:R0603")
      (libsource (lib "eagle-import") (part "R-EU_R0603"))
    )
    (comp (ref "R64")
      (value "3.9Mohm")
      (footprint "eagle-import:R0603")
      (libsource (lib "eagle-import") (part "R-EU_R0603"))
    )
    (comp (ref "R65")
      (value "3.9Mohm")
      (footprint "eagle-import:R0603")
      (libsource (lib "eagle-import") (part "R-EU_R0603"))
    )
    (comp (ref "R66")
      (value "3.9Mohm")
      (footprint "eagle-import:R0603")
      (libsource (lib "eagle-import") (part "R-EU_R0603"))
    )
    (comp (ref "R67")
      (value "3.9Mohm")
      (footprint "eagle-import:R0603")
      (libsource (lib "eagle-import") (part "R-EU_R0603"))
    )
    (comp (ref "R68")
      (value "3.9Mohm")
      (footprint "eagle-import:R0603")
      (libsource (lib "eagle-import") (part "R-EU_R0603"))
    )
    (comp (ref "R69")
      (value "3.9Mohm")
      (footprint "eagle-import:R0603")
      (libsource (lib "eagle-import") (part "R-EU_R0603"))
    )
    (comp (ref "R70")
      (value "3.9Mohm")
      (footprint "eagle-import:R0603")
      (libsource (lib "eagle-import") (part "R-EU_R0603"))
    )
    (comp (ref "R71")
      (value "3.9Mohm")
      (footprint "eagle-import:R0603")
      (libsource (lib "eagle-import") (part "R-EU_R0603"))
    )
    (comp (ref "R72")
      (value "3.9Mohm")
      (footprint "eagle-import:R0603")
      (libsource (lib "eagle-import") (part "R-EU_R0603"))
    )
    (comp (ref "R73")
      (value "3.9Mohm")
      (footprint "eagle-import:R0603")
      (libsource (lib "eagle-import") (part "R-EU_R0603"))
    )
    (comp (ref "R74")
      (value "3.9Mohm")
      (footprint "eagle-import:R0603")
      (libsource (lib "eagle-import") (part "R-EU_R0603"))
    )
    (comp (ref "R75")
      (value "3.9Mohm")
      (footprint "eagle-import:R0603")
      (libsource (lib "eagle-import") (part "R-EU_R0603"))
    )
    (comp (ref "R76")
      (value "3.9Mohm")
      (footprint "eagle-import:R0603")
      (libsource (lib "eagle-import") (part "R-EU_R0603"))
    )
    (comp (ref "R77")
      (value "3.9Mohm")
      (footprint "eagle-import:R0603")
      (libsource (lib "eagle-import") (part "R-EU_R0603"))
    )
    (comp (ref "R78")
      (value "3.9Mohm")
      (footprint "eagle-import:R0603")
      (libsource (lib "eagle-import") (part "R-EU_R0603"))
    )
    (comp (ref "R79")
      (value "3.9Mohm")
      (footprint "eagle-import:R0603")
      (libsource (lib "eagle-import") (part "R-EU_R0603"))
    )
    (comp (ref "R80")
      (value "3.9Mohm")
      (footprint "eagle-import:R0603")
      (libsource (lib "eagle-import") (part "R-EU_R0603"))
    )
    (comp (ref "R81")
      (value "3.9Mohm")
      (footprint "eagle-import:R0603")
      (libsource (lib "eagle-import") (part "R-EU_R0603"))
    )
    (comp (ref "R82")
      (value "3.9Mohm")
      (footprint "eagle-import:R0603")
      (libsource (lib "eagle-import") (part "R-EU_R0603"))
    )
    (comp (ref "R83")
      (value "3.9Mohm")
      (footprint "eagle-import:R0603")
      (libsource (lib "eagle-import") (part "R-EU_R0603"))
    )
    (comp (ref "R84")
      (value "3.9Mohm")
      (footprint "eagle-import:R0603")
      (libsource (lib "eagle-import") (part "R-EU_R0603"))
    )
    (comp (ref "R85")
      (value "3.9Mohm")
      (footprint "eagle-import:R0603")
      (libsource (lib "eagle-import") (part "R-EU_R0603"))
    )
    (comp (ref "R86")
      (value "3.9Mohm")
      (footprint "eagle-import:R0603")
      (libsource (lib "eagle-import") (part "R-EU_R0603"))
    )
    (comp (ref "R87")
      (value "3.9Mohm")
      (footprint "eagle-import:R0603")
      (libsource (lib "eagle-import") (part "R-EU_R0603"))
    )
    (comp (ref "R88")
      (value "3.9Mohm")
      (footprint "eagle-import:R0603")
      (libsource (lib "eagle-import") (part "R-EU_R0603"))
    )
    (comp (ref "R89")
      (value "3.9Mohm")
      (footprint "eagle-import:R0603")
      (libsource (lib "eagle-import") (part "R-EU_R0603"))
    )
    (comp (ref "R90")
      (value "3.9Mohm")
      (footprint "eagle-import:R0603")
      (libsource (lib "eagle-import") (part "R-EU_R0603"))
    )
    (comp (ref "R91")
      (value "3.9Mohm")
      (footprint "eagle-import:R0603")
      (libsource (lib "eagle-import") (part "R-EU_R0603"))
    )
    (comp (ref "R92")
      (value "3.9Mohm")
      (footprint "eagle-import:R0603")
      (libsource (lib "eagle-import") (part "R-EU_R0603"))
    )
    (comp (ref "R93")
      (value "3.9Mohm")
      (footprint "eagle-import:R0603")
      (libsource (lib "eagle-import") (part "R-EU_R0603"))
    )
    (comp (ref "R94")
      (value "3.9Mohm")
      (footprint "eagle-import:R0603")
      (libsource (lib "eagle-import") (part "R-EU_R0603"))
    )
    (comp (ref "R95")
      (value "3.9Mohm")
      (footprint "eagle-import:R0603")
      (libsource (lib "eagle-import") (part "R-EU_R0603"))
    )
    (comp (ref "R96")
      (value "3.9Mohm")
      (footprint "eagle-import:R0603")
      (libsource (lib "eagle-import") (part "R-EU_R0603"))
    )
    (comp (ref "R97")
      (value "3.9Mohm")
      (footprint "eagle-import:R0603")
      (libsource (lib "eagle-import") (part "R-EU_R0603"))
    )
    (comp (ref "U1")
      (value "74HC4067")
      (footprint "eagle-import:SSOP24")
      (libsource (lib "eagle-import") (part "MUX-1X16"))
    )
    (comp (ref "U2")
      (value "74HC4067")
      (footprint "eagle-import:SSOP24")
      (libsource (lib "eagle-import") (part "MUX-1X16"))
    )
    (comp (ref "U3")
      (value "74HC4067")
      (footprint "eagle-import:SSOP24")
      (libsource (lib "eagle-import") (part "MUX-1X16"))
    )
    (comp (ref "U4")
      (value "74HC4067")
      (footprint "eagle-import:SSOP24")
      (libsource (lib "eagle-import") (part "MUX-1X16"))
    )
    (comp (ref "U5")
      (value "74HC4067")
      (footprint "eagle-import:SSOP24")
      (libsource (lib "eagle-import") (part "MUX-1X16"))
    )
    (comp (ref "U6")
      (value "74HC4067")
      (footprint "eagle-import:SSOP24")
      (libsource (lib "eagle-import") (part "MUX-1X16"))
    )
  )
  (nets
    (net (code "1") (name "+5V") (class "Default")
      (node (ref "C1") (pin "1") (pinfunction "1_1") (pintype "passive"))
      (node (ref "C10") (pin "1") (pinfunction "1_1") (pintype "passive"))
      (node (ref "C11") (pin "1") (pinfunction "1_1") (pintype "passive"))
      (node (ref "C12") (pin "1") (pinfunction "1_1") (pintype "passive"))
      (node (ref "C13") (pin "1") (pinfunction "1_1") (pintype "passive"))
      (node (ref "C14") (pin "1") (pinfunction "1_1") (pintype "passive"))
      (node (ref "C15") (pin "1") (pinfunction "1_1") (pintype "passive"))
      (node (ref "C16") (pin "1") (pinfunction "1_1") (pintype "passive"))
      (node (ref "C17") (pin "1") (pinfunction "1_1") (pintype "passive"))
      (node (ref "C18") (pin "1") (pinfunction "1_1") (pintype "passive"))
      (node (ref "C19") (pin "1") (pinfunction "1_1") (pintype "passive"))
      (node (ref "C2") (pin "1") (pinfunction "1_1") (pintype "passive"))
      (node (ref "C20") (pin "1") (pinfunction "1_1") (pintype "passive"))
      (node (ref "C21") (pin "1") (pinfunction "1_1") (pintype "passive"))
      (node (ref "C22") (pin "1") (pinfunction "1_1") (pintype "passive"))
      (node (ref "C23") (pin "1") (pinfunction "1_1") (pintype "passive"))
      (node (ref "C25") (pin "1") (pinfunction "1_1") (pintype "passive"))
      (node (ref "C3") (pin "1") (pinfunction "1_1") (pintype "passive"))
      (node (ref "C4") (pin "1") (pinfunction "1_1") (pintype "passive"))
      (node (ref "C5") (pin "1") (pinfunction "1_1") (pintype "passive"))
      (node (ref "C6") (pin "1") (pinfunction "1_1") (pintype "passive"))
      (node (ref "C7") (pin "1") (pinfunction "1_1") (pintype "passive"))
      (node (ref "C8") (pin "1") (pinfunction "1_1") (pintype "passive"))
      (node (ref "C9") (pin "1") (pinfunction "1_1") (pintype "passive"))
      (node (ref "IC1") (pin "4") (pinfunction "V+_4") (pintype "power_in"))
      (node (ref "IC10") (pin "4") (pinfunction "V+_4") (pintype "power_in"))
      (node (ref "IC11") (pin "4") (pinfunction "V+_4") (pintype "power_in"))
      (node (ref "IC12") (pin "4") (pinfunction "V+_4") (pintype "power_in"))
      (node (ref "IC13") (pin "4") (pinfunction "V+_4") (pintype "power_in"))
      (node (ref "IC14") (pin "4") (pinfunction "V+_4") (pintype "power_in"))
      (node (ref "IC15") (pin "4") (pinfunction "V+_4") (pintype "power_in"))
      (node (ref "IC16") (pin "4") (pinfunction "V+_4") (pintype "power_in"))
      (node (ref "IC17") (pin "4") (pinfunction "V+_4") (pintype "power_in"))
      (node (ref "IC18") (pin "4") (pinfunction "V+_4") (pintype "power_in"))
      (node (ref "IC19") (pin "4") (pinfunction "V+_4") (pintype "power_in"))
      (node (ref "IC2") (pin "4") (pinfunction "V+_4") (pintype "power_in"))
      (node (ref "IC20") (pin "4") (pinfunction "V+_4") (pintype "power_in"))
      (node (ref "IC21") (pin "4") (pinfunction "V+_4") (pintype "power_in"))
      (node (ref "IC22") (pin "4") (pinfunction "V+_4") (pintype "power_in"))
      (node (ref "IC23") (pin "4") (pinfunction "V+_4") (pintype "power_in"))
      (node (ref "IC24") (pin "4") (pinfunction "V+_4") (pintype "power_in"))
      (node (ref "IC3") (pin "4") (pinfunction "V+_4") (pintype "power_in"))
      (node (ref "IC4") (pin "4") (pinfunction "V+_4") (pintype "power_in"))
      (node (ref "IC5") (pin "4") (pinfunction "V+_4") (pintype "power_in"))
      (node (ref "IC6") (pin "4") (pinfunction "V+_4") (pintype "power_in"))
      (node (ref "IC7") (pin "4") (pinfunction "V+_4") (pintype "power_in"))
      (node (ref "IC8") (pin "4") (pinfunction "V+_4") (pintype "power_in"))
      (node (ref "IC9") (pin "4") (pinfunction "V+_4") (pintype "power_in"))
      (node (ref "J2") (pin "6") (pinfunction "6_6") (pintype "passive"))
      (node (ref "U1") (pin "24") (pinfunction "VCC_24") (pintype "bidirectional"))
      (node (ref "U2") (pin "24") (pinfunction "VCC_24") (pintype "bidirectional"))
      (node (ref "U3") (pin "24") (pinfunction "VCC_24") (pintype "bidirectional"))
      (node (ref "U4") (pin "24") (pinfunction "VCC_24") (pintype "bidirectional"))
      (node (ref "U5") (pin "24") (pinfunction "VCC_24") (pintype "bidirectional"))
      (node (ref "U6") (pin "24") (pinfunction "VCC_24") (pintype "bidirectional"))
    )
    (net (code "2") (name "/AO1") (class "Default")
      (node (ref "IC10") (pin "1") (pinfunction "OUT_1") (pintype "output"))
      (node (ref "R11") (pin "2") (pinfunction "2_2") (pintype "passive"))
      (node (ref "U1") (pin "2") (pinfunction "CH7_2") (pintype "bidirectional"))
    )
    (net (code "3") (name "/AO2") (class "Default")
      (node (ref "IC10") (pin "7") (pinfunction "OUT_7") (pintype "output"))
      (node (ref "R22") (pin "2") (pinfunction "2_2") (pintype "passive"))
      (node (ref "U1") (pin "3") (pinfunction "CH6_3") (pintype "bidirectional"))
    )
    (net (code "4") (name "/AO3") (class "Default")
      (node (ref "IC11") (pin "1") (pinfunction "OUT_1") (pintype "output"))
      (node (ref "R12") (pin "2") (pinfunction "2_2") (pintype "passive"))
      (node (ref "U1") (pin "4") (pinfunction "CH5_4") (pintype "bidirectional"))
    )
    (net (code "5") (name "/AO4") (class "Default")
      (node (ref "IC11") (pin "7") (pinfunction "OUT_7") (pintype "output"))
      (node (ref "R23") (pin "2") (pinfunction "2_2") (pintype "passive"))
      (node (ref "U1") (pin "5") (pinfunction "CH4_5") (pintype "bidirectional"))
    )
    (net (code "6") (name "/AO5") (class "Default")
      (node (ref "IC8") (pin "1") (pinfunction "OUT_1") (pintype "output"))
      (node (ref "R9") (pin "2") (pinfunction "2_2") (pintype "passive"))
      (node (ref "U1") (pin "23") (pinfunction "CH8_23") (pintype "bidirectional"))
    )
    (net (code "7") (name "/AO6") (class "Default")
      (node (ref "IC8") (pin "7") (pinfunction "OUT_7") (pintype "output"))
      (node (ref "R20") (pin "2") (pinfunction "2_2") (pintype "passive"))
      (node (ref "U1") (pin "22") (pinfunction "CH9_22") (pintype "bidirectional"))
    )
    (net (code "8") (name "/AO7") (class "Default")
      (node (ref "IC7") (pin "1") (pinfunction "OUT_1") (pintype "output"))
      (node (ref "R8") (pin "2") (pinfunction "2_2") (pintype "passive"))
      (node (ref "U1") (pin "21") (pinfunction "CH10_21") (pintype "bidirectional"))
    )
    (net (code "9") (name "/AO8") (class "Default")
      (node (ref "IC7") (pin "7") (pinfunction "OUT_7") (pintype "output"))
      (node (ref "R19") (pin "2") (pinfunction "2_2") (pintype "passive"))
      (node (ref "U1") (pin "20") (pinfunction "CH11_20") (pintype "bidirectional"))
    )
    (net (code "10") (name "/AO9") (class "Default")
      (node (ref "IC10") (pin "14") (pinfunction "OUT_14") (pintype "output"))
      (node (ref "R38") (pin "2") (pinfunction "2_2") (pintype "passive"))
      (node (ref "U1") (pin "6") (pinfunction "CH3_6") (pintype "bidirectional"))
    )
    (net (code "11") (name "/AO10") (class "Default")
      (node (ref "IC10") (pin "8") (pinfunction "OUT_8") (pintype "output"))
      (node (ref "R30") (pin "2") (pinfunction "2_2") (pintype "passive"))
      (node (ref "U1") (pin "7") (pinfunction "CH2_7") (pintype "bidirectional"))
    )
    (net (code "12") (name "/AO11") (class "Default")
      (node (ref "IC11") (pin "14") (pinfunction "OUT_14") (pintype "output"))
      (node (ref "R39") (pin "2") (pinfunction "2_2") (pintype "passive"))
      (node (ref "U1") (pin "8") (pinfunction "CH1_8") (pintype "bidirectional"))
    )
    (net (code "13") (name "/AO12") (class "Default")
      (node (ref "IC11") (pin "8") (pinfunction "OUT_8") (pintype "output"))
      (node (ref "R31") (pin "2") (pinfunction "2_2") (pintype "passive"))
      (node (ref "U1") (pin "9") (pinfunction "CH0_9") (pintype "bidirectional"))
    )
    (net (code "14") (name "/AO13") (class "Default")
      (node (ref "IC8") (pin "14") (pinfunction "OUT_14") (pintype "output"))
      (node (ref "R36") (pin "2") (pinfunction "2_2") (pintype "passive"))
      (node (ref "U1") (pin "19") (pinfunction "CH12_19") (pintype "bidirectional"))
    )
    (net (code "15") (name "/AO14") (class "Default")
      (node (ref "IC8") (pin "8") (pinfunction "OUT_8") (pintype "output"))
      (node (ref "R27") (pin "2") (pinfunction "2_2") (pintype "passive"))
      (node (ref "U1") (pin "18") (pinfunction "CH13_18") (pintype "bidirectional"))
    )
    (net (code "16") (name "/AO15") (class "Default")
      (node (ref "IC7") (pin "14") (pinfunction "OUT_14") (pintype "output"))
      (node (ref "R35") (pin "2") (pinfunction "2_2") (pintype "passive"))
      (node (ref "U1") (pin "17") (pinfunction "CH14_17") (pintype "bidirectional"))
    )
    (net (code "17") (name "/AO16") (class "Default")
      (node (ref "IC7") (pin "8") (pinfunction "OUT_8") (pintype "output"))
      (node (ref "R26") (pin "2") (pinfunction "2_2") (pintype "passive"))
      (node (ref "U1") (pin "16") (pinfunction "CH15_16") (pintype "bidirectional"))
    )
    (net (code "18") (name "/AR0") (class "Default")
      (node (ref "J1") (pin "1") (pinfunction "1_1") (pintype "passive"))
      (node (ref "U1") (pin "1") (pinfunction "COM_1") (pintype "bidirectional"))
    )
    (net (code "19") (name "/AR1") (class "Default")
      (node (ref "J1") (pin "2") (pinfunction "2_2") (pintype "passive"))
      (node (ref "U3") (pin "1") (pinfunction "COM_1") (pintype "bidirectional"))
    )
    (net (code "20") (name "/AR2") (class "Default")
      (node (ref "J1") (pin "3") (pinfunction "3_3") (pintype "passive"))
      (node (ref "U5") (pin "1") (pinfunction "COM_1") (pintype "bidirectional"))
    )
    (net (code "21") (name "/AR3") (class "Default")
      (node (ref "J1") (pin "4") (pinfunction "4_4") (pintype "passive"))
      (node (ref "U2") (pin "1") (pinfunction "COM_1") (pintype "bidirectional"))
    )
    (net (code "22") (name "/AR4") (class "Default")
      (node (ref "J1") (pin "5") (pinfunction "5_5") (pintype "passive"))
      (node (ref "U4") (pin "1") (pinfunction "COM_1") (pintype "bidirectional"))
    )
    (net (code "23") (name "/AR5") (class "Default")
      (node (ref "J1") (pin "6") (pinfunction "6_6") (pintype "passive"))
      (node (ref "U6") (pin "1") (pinfunction "COM_1") (pintype "bidirectional"))
    )
    (net (code "24") (name "/BO1") (class "Default")
      (node (ref "IC17") (pin "1") (pinfunction "OUT_1") (pintype "output"))
      (node (ref "R66") (pin "2") (pinfunction "2_2") (pintype "passive"))
      (node (ref "U3") (pin "2") (pinfunction "CH7_2") (pintype "bidirectional"))
    )
    (net (code "25") (name "/BO2") (class "Default")
      (node (ref "IC17") (pin "7") (pinfunction "OUT_7") (pintype "output"))
      (node (ref "R77") (pin "2") (pinfunction "2_2") (pintype "passive"))
      (node (ref "U3") (pin "3") (pinfunction "CH6_3") (pintype "bidirectional"))
    )
    (net (code "26") (name "/BO3") (class "Default")
      (node (ref "IC20") (pin "1") (pinfunction "OUT_1") (pintype "output"))
      (node (ref "R70") (pin "2") (pinfunction "2_2") (pintype "passive"))
      (node (ref "U3") (pin "4") (pinfunction "CH5_4") (pintype "bidirectional"))
    )
    (net (code "27") (name "/BO4") (class "Default")
      (node (ref "IC20") (pin "7") (pinfunction "OUT_7") (pintype "output"))
      (node (ref "R80") (pin "2") (pinfunction "2_2") (pintype "passive"))
      (node (ref "U3") (pin "5") (pinfunction "CH4_5") (pintype "bidirectional"))
    )
    (net (code "28") (name "/BO5") (class "Default")
      (node (ref "IC2") (pin "1") (pinfunction "OUT_1") (pintype "output"))
      (node (ref "R5") (pin "2") (pinfunction "2_2") (pintype "passive"))
      (node (ref "U3") (pin "23") (pinfunction "CH8_23") (pintype "bidirectional"))
    )
    (net (code "29") (name "/BO6") (class "Default")
      (node (ref "IC2") (pin "7") (pinfunction "OUT_7") (pintype "output"))
      (node (ref "R18") (pin "2") (pinfunction "2_2") (pintype "passive"))
      (node (ref "U3") (pin "22") (pinfunction "CH9_22") (pintype "bidirectional"))
    )
    (net (code "30") (name "/BO7") (class "Default")
      (node (ref "IC1") (pin "1") (pinfunction "OUT_1") (pintype "output"))
      (node (ref "R4") (pin "2") (pinfunction "2_2") (pintype "passive"))
      (node (ref "U3") (pin "21") (pinfunction "CH10_21") (pintype "bidirectional"))
    )
    (net (code "31") (name "/BO8") (class "Default")
      (node (ref "IC1") (pin "7") (pinfunction "OUT_7") (pintype "output"))
      (node (ref "R15") (pin "2") (pinfunction "2_2") (pintype "passive"))
      (node (ref "U3") (pin "20") (pinfunction "CH11_20") (pintype "bidirectional"))
    )
    (net (code "32") (name "/BO9") (class "Default")
      (node (ref "IC17") (pin "14") (pinfunction "OUT_14") (pintype "output"))
      (node (ref "R90") (pin "2") (pinfunction "2_2") (pintype "passive"))
      (node (ref "U3") (pin "6") (pinfunction "CH3_6") (pintype "bidirectional"))
    )
    (net (code "33") (name "/BO10") (class "Default")
      (node (ref "IC17") (pin "8") (pinfunction "OUT_8") (pintype "output"))
      (node (ref "R83") (pin "2") (pinfunction "2_2") (pintype "passive"))
      (node (ref "U3") (pin "7") (pinfunction "CH2_7") (pintype "bidirectional"))
    )
    (net (code "34") (name "/BO11") (class "Default")
      (node (ref "IC20") (pin "14") (pinfunction "OUT_14") (pintype "output"))
      (node (ref "R96") (pin "2") (pinfunction "2_2") (pintype "passive"))
      (node (ref "U3") (pin "8") (pinfunction "CH1_8") (pintype "bidirectional"))
    )
    (net (code "35") (name "/BO12") (class "Default")
      (node (ref "IC20") (pin "8") (pinfunction "OUT_8") (pintype "output"))
      (node (ref "R87") (pin "2") (pinfunction "2_2") (pintype "passive"))
      (node (ref "U3") (pin "9") (pinfunction "CH0_9") (pintype "bidirectional"))
    )
    (net (code "36") (name "/BO13") (class "Default")
      (node (ref "IC2") (pin "14") (pinfunction "OUT_14") (pintype "output"))
      (node (ref "R41") (pin "2") (pinfunction "2_2") (pintype "passive"))
      (node (ref "U3") (pin "19") (pinfunction "CH12_19") (pintype "bidirectional"))
    )
    (net (code "37") (name "/BO14") (class "Default")
      (node (ref "IC2") (pin "8") (pinfunction "OUT_8") (pintype "output"))
      (node (ref "R24") (pin "2") (pinfunction "2_2") (pintype "passive"))
      (node (ref "U3") (pin "18") (pinfunction "CH13_18") (pintype "bidirectional"))
    )
    (net (code "38") (name "/BO15") (class "Default")
      (node (ref "IC1") (pin "14") (pinfunction "OUT_14") (pintype "output"))
      (node (ref "R44") (pin "2") (pinfunction "2_2") (pintype "passive"))
      (node (ref "U3") (pin "17") (pinfunction "CH14_17") (pintype "bidirectional"))
    )
    (net (code "39") (name "/BO16") (class "Default")
      (node (ref "IC1") (pin "8") (pinfunction "OUT_8") (pintype "output"))
      (node (ref "R25") (pin "2") (pinfunction "2_2") (pintype "passive"))
      (node (ref "U3") (pin "16") (pinfunction "CH15_16") (pintype "bidirectional"))
    )
    (net (code "40") (name "/CO1") (class "Default")
      (node (ref "IC13") (pin "1") (pinfunction "OUT_1") (pintype "output"))
      (node (ref "R49") (pin "2") (pinfunction "2_2") (pintype "passive"))
      (node (ref "U5") (pin "2") (pinfunction "CH7_2") (pintype "bidirectional"))
    )
    (net (code "41") (name "/CO2") (class "Default")
      (node (ref "IC13") (pin "7") (pinfunction "OUT_7") (pintype "output"))
      (node (ref "R55") (pin "2") (pinfunction "2_2") (pintype "passive"))
      (node (ref "U5") (pin "3") (pinfunction "CH6_3") (pintype "bidirectional"))
    )
    (net (code "42") (name "/CO3") (class "Default")
      (node (ref "IC12") (pin "1") (pinfunction "OUT_1") (pintype "output"))
      (node (ref "R48") (pin "2") (pinfunction "2_2") (pintype "passive"))
      (node (ref "U5") (pin "4") (pinfunction "CH5_4") (pintype "bidirectional"))
    )
    (net (code "43") (name "/CO4") (class "Default")
      (node (ref "IC12") (pin "7") (pinfunction "OUT_7") (pintype "output"))
      (node (ref "R54") (pin "2") (pinfunction "2_2") (pintype "passive"))
      (node (ref "U5") (pin "5") (pinfunction "CH4_5") (pintype "bidirectional"))
    )
    (net (code "44") (name "/CO5") (class "Default")
      (node (ref "IC23") (pin "1") (pinfunction "OUT_1") (pintype "output"))
      (node (ref "R72") (pin "2") (pinfunction "2_2") (pintype "passive"))
      (node (ref "U5") (pin "23") (pinfunction "CH8_23") (pintype "bidirectional"))
    )
    (net (code "45") (name "/CO6") (class "Default")
      (node (ref "IC23") (pin "7") (pinfunction "OUT_7") (pintype "output"))
      (node (ref "R76") (pin "2") (pinfunction "2_2") (pintype "passive"))
      (node (ref "U5") (pin "22") (pinfunction "CH9_22") (pintype "bidirectional"))
    )
    (net (code "46") (name "/CO7") (class "Default")
      (node (ref "IC19") (pin "1") (pinfunction "OUT_1") (pintype "output"))
      (node (ref "R71") (pin "2") (pinfunction "2_2") (pintype "passive"))
      (node (ref "U5") (pin "21") (pinfunction "CH10_21") (pintype "bidirectional"))
    )
    (net (code "47") (name "/CO8") (class "Default")
      (node (ref "IC19") (pin "7") (pinfunction "OUT_7") (pintype "output"))
      (node (ref "R75") (pin "2") (pinfunction "2_2") (pintype "passive"))
      (node (ref "U5") (pin "20") (pinfunction "CH11_20") (pintype "bidirectional"))
    )
    (net (code "48") (name "/CO9") (class "Default")
      (node (ref "IC13") (pin "14") (pinfunction "OUT_14") (pintype "output"))
      (node (ref "R65") (pin "2") (pinfunction "2_2") (pintype "passive"))
      (node (ref "U5") (pin "6") (pinfunction "CH3_6") (pintype "bidirectional"))
    )
    (net (code "49") (name "/CO10") (class "Default")
      (node (ref "IC13") (pin "8") (pinfunction "OUT_8") (pintype "output"))
      (node (ref "R60") (pin "2") (pinfunction "2_2") (pintype "passive"))
      (node (ref "U5") (pin "7") (pinfunction "CH2_7") (pintype "bidirectional"))
    )
    (net (code "50") (name "/CO11") (class "Default")
      (node (ref "IC12") (pin "14") (pinfunction "OUT_14") (pintype "output"))
      (node (ref "R64") (pin "2") (pinfunction "2_2") (pintype "passive"))
      (node (ref "U5") (pin "8") (pinfunction "CH1_8") (pintype "bidirectional"))
    )
    (net (code "51") (name "/CO12") (class "Default")
      (node (ref "IC12") (pin "8") (pinfunction "OUT_8") (pintype "output"))
      (node (ref "R59") (pin "2") (pinfunction "2_2") (pintype "passive"))
      (node (ref "U5") (pin "9") (pinfunction "CH0_9") (pintype "bidirectional"))
    )
    (net (code "52") (name "/CO13") (class "Default")
      (node (ref "IC23") (pin "14") (pinfunction "OUT_14") (pintype "output"))
      (node (ref "R94") (pin "2") (pinfunction "2_2") (pintype "passive"))
      (node (ref "U5") (pin "19") (pinfunction "CH12_19") (pintype "bidirectional"))
    )
    (net (code "53") (name "/CO14") (class "Default")
      (node (ref "IC23") (pin "8") (pinfunction "OUT_8") (pintype "output"))
      (node (ref "R82") (pin "2") (pinfunction "2_2") (pintype "passive"))
      (node (ref "U5") (pin "18") (pinfunction "CH13_18") (pintype "bidirectional"))
    )
    (net (code "54") (name "/CO15") (class "Default")
      (node (ref "IC19") (pin "14") (pinfunction "OUT_14") (pintype "output"))
      (node (ref "R92") (pin "2") (pinfunction "2_2") (pintype "passive"))
      (node (ref "U5") (pin "17") (pinfunction "CH14_17") (pintype "bidirectional"))
    )
    (net (code "55") (name "/CO16") (class "Default")
      (node (ref "IC19") (pin "8") (pinfunction "OUT_8") (pintype "output"))
      (node (ref "R86") (pin "2") (pinfunction "2_2") (pintype "passive"))
      (node (ref "U5") (pin "16") (pinfunction "CH15_16") (pintype "bidirectional"))
    )
    (net (code "56") (name "/DO1") (class "Default")
      (node (ref "IC6") (pin "1") (pinfunction "OUT_1") (pintype "output"))
      (node (ref "R1") (pin "2") (pinfunction "2_2") (pintype "passive"))
      (node (ref "U2") (pin "2") (pinfunction "CH7_2") (pintype "bidirectional"))
    )
    (net (code "57") (name "/DO2") (class "Default")
      (node (ref "IC6") (pin "7") (pinfunction "OUT_7") (pintype "output"))
      (node (ref "R14") (pin "2") (pinfunction "2_2") (pintype "passive"))
      (node (ref "U2") (pin "3") (pinfunction "CH6_3") (pintype "bidirectional"))
    )
    (net (code "58") (name "/DO3") (class "Default")
      (node (ref "IC16") (pin "1") (pinfunction "OUT_1") (pintype "output"))
      (node (ref "R47") (pin "2") (pinfunction "2_2") (pintype "passive"))
      (node (ref "U2") (pin "4") (pinfunction "CH5_4") (pintype "bidirectional"))
    )
    (net (code "59") (name "/DO4") (class "Default")
      (node (ref "IC16") (pin "7") (pinfunction "OUT_7") (pintype "output"))
      (node (ref "R51") (pin "2") (pinfunction "2_2") (pintype "passive"))
      (node (ref "U2") (pin "5") (pinfunction "CH4_5") (pintype "bidirectional"))
    )
    (net (code "60") (name "/DO5") (class "Default")
      (node (ref "IC18") (pin "1") (pinfunction "OUT_1") (pintype "output"))
      (node (ref "R69") (pin "2") (pinfunction "2_2") (pintype "passive"))
      (node (ref "U2") (pin "23") (pinfunction "CH8_23") (pintype "bidirectional"))
    )
    (net (code "61") (name "/DO6") (class "Default")
      (node (ref "IC18") (pin "7") (pinfunction "OUT_7") (pintype "output"))
      (node (ref "R74") (pin "2") (pinfunction "2_2") (pintype "passive"))
      (node (ref "U2") (pin "22") (pinfunction "CH9_22") (pintype "bidirectional"))
    )
    (net (code "62") (name "/DO7") (class "Default")
      (node (ref "IC4") (pin "1") (pinfunction "OUT_1") (pintype "output"))
      (node (ref "R3") (pin "2") (pinfunction "2_2") (pintype "passive"))
      (node (ref "U2") (pin "21") (pinfunction "CH10_21") (pintype "bidirectional"))
    )
    (net (code "63") (name "/DO8") (class "Default")
      (node (ref "IC4") (pin "7") (pinfunction "OUT_7") (pintype "output"))
      (node (ref "R16") (pin "2") (pinfunction "2_2") (pintype "passive"))
      (node (ref "U2") (pin "20") (pinfunction "CH11_20") (pintype "bidirectional"))
    )
    (net (code "64") (name "/DO9") (class "Default")
      (node (ref "IC6") (pin "14") (pinfunction "OUT_14") (pintype "output"))
      (node (ref "R42") (pin "2") (pinfunction "2_2") (pintype "passive"))
      (node (ref "U2") (pin "6") (pinfunction "CH3_6") (pintype "bidirectional"))
    )
    (net (code "65") (name "/DO10") (class "Default")
      (node (ref "IC6") (pin "8") (pinfunction "OUT_8") (pintype "output"))
      (node (ref "R29") (pin "2") (pinfunction "2_2") (pintype "passive"))
      (node (ref "U2") (pin "7") (pinfunction "CH2_7") (pintype "bidirectional"))
    )
    (net (code "66") (name "/DO11") (class "Default")
      (node (ref "IC16") (pin "14") (pinfunction "OUT_14") (pintype "output"))
      (node (ref "R61") (pin "2") (pinfunction "2_2") (pintype "passive"))
      (node (ref "U2") (pin "8") (pinfunction "CH1_8") (pintype "bidirectional"))
    )
    (net (code "67") (name "/DO12") (class "Default")
      (node (ref "IC16") (pin "8") (pinfunction "OUT_8") (pintype "output"))
      (node (ref "R57") (pin "2") (pinfunction "2_2") (pintype "passive"))
      (node (ref "U2") (pin "9") (pinfunction "CH0_9") (pintype "bidirectional"))
    )
    (net (code "68") (name "/DO13") (class "Default")
      (node (ref "IC18") (pin "14") (pinfunction "OUT_14") (pintype "output"))
      (node (ref "R91") (pin "2") (pinfunction "2_2") (pintype "passive"))
      (node (ref "U2") (pin "19") (pinfunction "CH12_19") (pintype "bidirectional"))
    )
    (net (code "69") (name "/DO14") (class "Default")
      (node (ref "IC18") (pin "8") (pinfunction "OUT_8") (pintype "output"))
      (node (ref "R85") (pin "2") (pinfunction "2_2") (pintype "passive"))
      (node (ref "U2") (pin "18") (pinfunction "CH13_18") (pintype "bidirectional"))
    )
    (net (code "70") (name "/DO15") (class "Default")
      (node (ref "IC4") (pin "14") (pinfunction "OUT_14") (pintype "output"))
      (node (ref "R40") (pin "2") (pinfunction "2_2") (pintype "passive"))
      (node (ref "U2") (pin "17") (pinfunction "CH14_17") (pintype "bidirectional"))
    )
    (net (code "71") (name "/DO16") (class "Default")
      (node (ref "IC4") (pin "8") (pinfunction "OUT_8") (pintype "output"))
      (node (ref "R32") (pin "2") (pinfunction "2_2") (pintype "passive"))
      (node (ref "U2") (pin "16") (pinfunction "CH15_16") (pintype "bidirectional"))
    )
    (net (code "72") (name "/EO1") (class "Default")
      (node (ref "IC14") (pin "1") (pinfunction "OUT_1") (pintype "output"))
      (node (ref "R46") (pin "2") (pinfunction "2_2") (pintype "passive"))
      (node (ref "U4") (pin "2") (pinfunction "CH7_2") (pintype "bidirectional"))
    )
    (net (code "73") (name "/EO2") (class "Default")
      (node (ref "IC14") (pin "7") (pinfunction "OUT_7") (pintype "output"))
      (node (ref "R52") (pin "2") (pinfunction "2_2") (pintype "passive"))
      (node (ref "U4") (pin "3") (pinfunction "CH6_3") (pintype "bidirectional"))
    )
    (net (code "74") (name "/EO3") (class "Default")
      (node (ref "IC24") (pin "1") (pinfunction "OUT_1") (pintype "output"))
      (node (ref "R67") (pin "2") (pinfunction "2_2") (pintype "passive"))
      (node (ref "U4") (pin "4") (pinfunction "CH5_4") (pintype "bidirectional"))
    )
    (net (code "75") (name "/EO4") (class "Default")
      (node (ref "IC24") (pin "7") (pinfunction "OUT_7") (pintype "output"))
      (node (ref "R78") (pin "2") (pinfunction "2_2") (pintype "passive"))
      (node (ref "U4") (pin "5") (pinfunction "CH4_5") (pintype "bidirectional"))
    )
    (net (code "76") (name "/EO5") (class "Default")
      (node (ref "IC5") (pin "1") (pinfunction "OUT_1") (pintype "output"))
      (node (ref "R7") (pin "2") (pinfunction "2_2") (pintype "passive"))
      (node (ref "U4") (pin "23") (pinfunction "CH8_23") (pintype "bidirectional"))
    )
    (net (code "77") (name "/EO6") (class "Default")
      (node (ref "IC5") (pin "7") (pinfunction "OUT_7") (pintype "output"))
      (node (ref "R13") (pin "2") (pinfunction "2_2") (pintype "passive"))
      (node (ref "U4") (pin "22") (pinfunction "CH9_22") (pintype "bidirectional"))
    )
    (net (code "78") (name "/EO7") (class "Default")
      (node (ref "IC15") (pin "1") (pinfunction "OUT_1") (pintype "output"))
      (node (ref "R50") (pin "2") (pinfunction "2_2") (pintype "passive"))
      (node (ref "U4") (pin "21") (pinfunction "CH10_21") (pintype "bidirectional"))
    )
    (net (code "79") (name "/EO8") (class "Default")
      (node (ref "IC15") (pin "7") (pinfunction "OUT_7") (pintype "output"))
      (node (ref "R53") (pin "2") (pinfunction "2_2") (pintype "passive"))
      (node (ref "U4") (pin "20") (pinfunction "CH11_20") (pintype "bidirectional"))
    )
    (net (code "80") (name "/EO9") (class "Default")
      (node (ref "IC14") (pin "14") (pinfunction "OUT_14") (pintype "output"))
      (node (ref "R62") (pin "2") (pinfunction "2_2") (pintype "passive"))
      (node (ref "U4") (pin "6") (pinfunction "CH3_6") (pintype "bidirectional"))
    )
    (net (code "81") (name "/EO10") (class "Default")
      (node (ref "IC14") (pin "8") (pinfunction "OUT_8") (pintype "output"))
      (node (ref "R58") (pin "2") (pinfunction "2_2") (pintype "passive"))
      (node (ref "U4") (pin "7") (pinfunction "CH2_7") (pintype "bidirectional"))
    )
    (net (code "82") (name "/EO11") (class "Default")
      (node (ref "IC24") (pin "14") (pinfunction "OUT_14") (pintype "output"))
      (node (ref "R95") (pin "2") (pinfunction "2_2") (pintype "passive"))
      (node (ref "U4") (pin "8") (pinfunction "CH1_8") (pintype "bidirectional"))
    )
    (net (code "83") (name "/EO12") (class "Default")
      (node (ref "IC24") (pin "8") (pinfunction "OUT_8") (pintype "output"))
      (node (ref "R84") (pin "2") (pinfunction "2_2") (pintype "passive"))
      (node (ref "U4") (pin "9") (pinfunction "CH0_9") (pintype "bidirectional"))
    )
    (net (code "84") (name "/EO13") (class "Default")
      (node (ref "IC5") (pin "14") (pinfunction "OUT_14") (pintype "output"))
      (node (ref "R43") (pin "2") (pinfunction "2_2") (pintype "passive"))
      (node (ref "U4") (pin "19") (pinfunction "CH12_19") (pintype "bidirectional"))
    )
    (net (code "85") (name "/EO14") (class "Default")
      (node (ref "IC5") (pin "8") (pinfunction "OUT_8") (pintype "output"))
      (node (ref "R33") (pin "2") (pinfunction "2_2") (pintype "passive"))
      (node (ref "U4") (pin "18") (pinfunction "CH13_18") (pintype "bidirectional"))
    )
    (net (code "86") (name "/EO15") (class "Default")
      (node (ref "IC15") (pin "14") (pinfunction "OUT_14") (pintype "output"))
      (node (ref "R63") (pin "2") (pinfunction "2_2") (pintype "passive"))
      (node (ref "U4") (pin "17") (pinfunction "CH14_17") (pintype "bidirectional"))
    )
    (net (code "87") (name "/EO16") (class "Default")
      (node (ref "IC15") (pin "8") (pinfunction "OUT_8") (pintype "output"))
      (node (ref "R56") (pin "2") (pinfunction "2_2") (pintype "passive"))
      (node (ref "U4") (pin "16") (pinfunction "CH15_16") (pintype "bidirectional"))
    )
    (net (code "88") (name "/FO1") (class "Default")
      (node (ref "IC22") (pin "1") (pinfunction "OUT_1") (pintype "output"))
      (node (ref "R68") (pin "2") (pinfunction "2_2") (pintype "passive"))
      (node (ref "U6") (pin "2") (pinfunction "CH7_2") (pintype "bidirectional"))
    )
    (net (code "89") (name "/FO2") (class "Default")
      (node (ref "IC22") (pin "7") (pinfunction "OUT_7") (pintype "output"))
      (node (ref "R79") (pin "2") (pinfunction "2_2") (pintype "passive"))
      (node (ref "U6") (pin "3") (pinfunction "CH6_3") (pintype "bidirectional"))
    )
    (net (code "90") (name "/FO3") (class "Default")
      (node (ref "IC3") (pin "1") (pinfunction "OUT_1") (pintype "output"))
      (node (ref "R2") (pin "2") (pinfunction "2_2") (pintype "passive"))
      (node (ref "U6") (pin "4") (pinfunction "CH5_4") (pintype "bidirectional"))
    )
    (net (code "91") (name "/FO4") (class "Default")
      (node (ref "IC3") (pin "7") (pinfunction "OUT_7") (pintype "output"))
      (node (ref "R17") (pin "2") (pinfunction "2_2") (pintype "passive"))
      (node (ref "U6") (pin "5") (pinfunction "CH4_5") (pintype "bidirectional"))
    )
    (net (code "92") (name "/FO5") (class "Default")
      (node (ref "IC9") (pin "1") (pinfunction "OUT_1") (pintype "output"))
      (node (ref "R10") (pin "2") (pinfunction "2_2") (pintype "passive"))
      (node (ref "U6") (pin "23") (pinfunction "CH8_23") (pintype "bidirectional"))
    )
    (net (code "93") (name "/FO6") (class "Default")
      (node (ref "IC9") (pin "7") (pinfunction "OUT_7") (pintype "output"))
      (node (ref "R21") (pin "2") (pinfunction "2_2") (pintype "passive"))
      (node (ref "U6") (pin "22") (pinfunction "CH9_22") (pintype "bidirectional"))
    )
    (net (code "94") (name "/FO7") (class "Default")
      (node (ref "IC21") (pin "1") (pinfunction "OUT_1") (pintype "output"))
      (node (ref "R73") (pin "2") (pinfunction "2_2") (pintype "passive"))
      (node (ref "U6") (pin "21") (pinfunction "CH10_21") (pintype "bidirectional"))
    )
    (net (code "95") (name "/FO8") (class "Default")
      (node (ref "IC21") (pin "7") (pinfunction "OUT_7") (pintype "output"))
      (node (ref "R81") (pin "2") (pinfunction "2_2") (pintype "passive"))
      (node (ref "U6") (pin "20") (pinfunction "CH11_20") (pintype "bidirectional"))
    )
    (net (code "96") (name "/FO9") (class "Default")
      (node (ref "IC22") (pin "14") (pinfunction "OUT_14") (pintype "output"))
      (node (ref "R93") (pin "2") (pinfunction "2_2") (pintype "passive"))
      (node (ref "U6") (pin "6") (pinfunction "CH3_6") (pintype "bidirectional"))
    )
    (net (code "97") (name "/FO10") (class "Default")
      (node (ref "IC22") (pin "8") (pinfunction "OUT_8") (pintype "output"))
      (node (ref "R88") (pin "2") (pinfunction "2_2") (pintype "passive"))
      (node (ref "U6") (pin "7") (pinfunction "CH2_7") (pintype "bidirectional"))
    )
    (net (code "98") (name "/FO11") (class "Default")
      (node (ref "IC3") (pin "14") (pinfunction "OUT_14") (pintype "output"))
      (node (ref "R45") (pin "2") (pinfunction "2_2") (pintype "passive"))
      (node (ref "U6") (pin "8") (pinfunction "CH1_8") (pintype "bidirectional"))
    )
    (net (code "99") (name "/FO12") (class "Default")
      (node (ref "IC3") (pin "8") (pinfunction "OUT_8") (pintype "output"))
      (node (ref "R34") (pin "2") (pinfunction "2_2") (pintype "passive"))
      (node (ref "U6") (pin "9") (pinfunction "CH0_9") (pintype "bidirectional"))
    )
    (net (code "100") (name "/FO13") (class "Default")
      (node (ref "IC9") (pin "14") (pinfunction "OUT_14") (pintype "output"))
      (node (ref "R37") (pin "2") (pinfunction "2_2") (pintype "passive"))
      (node (ref "U6") (pin "19") (pinfunction "CH12_19") (pintype "bidirectional"))
    )
    (net (code "101") (name "/FO14") (class "Default")
      (node (ref "IC9") (pin "8") (pinfunction "OUT_8") (pintype "output"))
      (node (ref "R28") (pin "2") (pinfunction "2_2") (pintype "passive"))
      (node (ref "U6") (pin "18") (pinfunction "CH13_18") (pintype "bidirectional"))
    )
    (net (code "102") (name "/FO15") (class "Default")
      (node (ref "IC21") (pin "14") (pinfunction "OUT_14") (pintype "output"))
      (node (ref "R97") (pin "2") (pinfunction "2_2") (pintype "passive"))
      (node (ref "U6") (pin "17") (pinfunction "CH14_17") (pintype "bidirectional"))
    )
    (net (code "103") (name "/FO16") (class "Default")
      (node (ref "IC21") (pin "8") (pinfunction "OUT_8") (pintype "output"))
      (node (ref "R89") (pin "2") (pinfunction "2_2") (pintype "passive"))
      (node (ref "U6") (pin "16") (pinfunction "CH15_16") (pintype "bidirectional"))
    )
    (net (code "104") (name "/PD1") (class "Default")
      (node (ref "IC10") (pin "2") (pinfunction "-IN_2") (pintype "input"))
      (node (ref "PHD1") (pin "2") (pinfunction "2_2") (pintype "bidirectional"))
      (node (ref "R11") (pin "1") (pinfunction "1_1") (pintype "passive"))
    )
    (net (code "105") (name "/PD2") (class "Default")
      (node (ref "IC10") (pin "6") (pinfunction "-IN_6") (pintype "input"))
      (node (ref "PHD2") (pin "2") (pinfunction "2_2") (pintype "bidirectional"))
      (node (ref "R22") (pin "1") (pinfunction "1_1") (pintype "passive"))
    )
    (net (code "106") (name "/PD3") (class "Default")
      (node (ref "IC11") (pin "2") (pinfunction "-IN_2") (pintype "input"))
      (node (ref "PHD3") (pin "2") (pinfunction "2_2") (pintype "bidirectional"))
      (node (ref "R12") (pin "1") (pinfunction "1_1") (pintype "passive"))
    )
    (net (code "107") (name "/PD4") (class "Default")
      (node (ref "IC11") (pin "6") (pinfunction "-IN_6") (pintype "input"))
      (node (ref "PHD4") (pin "2") (pinfunction "2_2") (pintype "bidirectional"))
      (node (ref "R23") (pin "1") (pinfunction "1_1") (pintype "passive"))
    )
    (net (code "108") (name "/PD5") (class "Default")
      (node (ref "IC8") (pin "2") (pinfunction "-IN_2") (pintype "input"))
      (node (ref "PHD5") (pin "2") (pinfunction "2_2") (pintype "bidirectional"))
      (node (ref "R9") (pin "1") (pinfunction "1_1") (pintype "passive"))
    )
    (net (code "109") (name "/PD6") (class "Default")
      (node (ref "IC8") (pin "6") (pinfunction "-IN_6") (pintype "input"))
      (node (ref "PHD6") (pin "2") (pinfunction "2_2") (pintype "bidirectional"))
      (node (ref "R20") (pin "1") (pinfunction "1_1") (pintype "passive"))
    )
    (net (code "110") (name "/PD7") (class "Default")
      (node (ref "IC7") (pin "2") (pinfunction "-IN_2") (pintype "input"))
      (node (ref "PHD7") (pin "2") (pinfunction "2_2") (pintype "bidirectional"))
      (node (ref "R8") (pin "1") (pinfunction "1_1") (pintype "passive"))
    )
    (net (code "111") (name "/PD8") (class "Default")
      (node (ref "IC7") (pin "6") (pinfunction "-IN_6") (pintype "input"))
      (node (ref "PHD8") (pin "2") (pinfunction "2_2") (pintype "bidirectional"))
      (node (ref "R19") (pin "1") (pinfunction "1_1") (pintype "passive"))
    )
    (net (code "112") (name "/PD9") (class "Default")
      (node (ref "IC10") (pin "13") (pinfunction "-IN_13") (pintype "input"))
      (node (ref "PHD9") (pin "2") (pinfunction "2_2") (pintype "bidirectional"))
      (node (ref "R38") (pin "1") (pinfunction "1_1") (pintype "passive"))
    )
    (net (code "113") (name "/PD10") (class "Default")
      (node (ref "IC10") (pin "9") (pinfunction "-IN_9") (pintype "input"))
      (node (ref "PHD10") (pin "2") (pinfunction "2_2") (pintype "bidirectional"))
      (node (ref "R30") (pin "1") (pinfunction "1_1") (pintype "passive"))
    )
    (net (code "114") (name "/PD11") (class "Default")
      (node (ref "IC11") (pin "13") (pinfunction "-IN_13") (pintype "input"))
      (node (ref "PHD11") (pin "2") (pinfunction "2_2") (pintype "bidirectional"))
      (node (ref "R39") (pin "1") (pinfunction "1_1") (pintype "passive"))
    )
    (net (code "115") (name "/PD12") (class "Default")
      (node (ref "IC11") (pin "9") (pinfunction "-IN_9") (pintype "input"))
      (node (ref "PHD12") (pin "2") (pinfunction "2_2") (pintype "bidirectional"))
      (node (ref "R31") (pin "1") (pinfunction "1_1") (pintype "passive"))
    )
    (net (code "116") (name "/PD13") (class "Default")
      (node (ref "IC8") (pin "13") (pinfunction "-IN_13") (pintype "input"))
      (node (ref "PHD13") (pin "2") (pinfunction "2_2") (pintype "bidirectional"))
      (node (ref "R36") (pin "1") (pinfunction "1_1") (pintype "passive"))
    )
    (net (code "117") (name "/PD14") (class "Default")
      (node (ref "IC8") (pin "9") (pinfunction "-IN_9") (pintype "input"))
      (node (ref "PHD14") (pin "2") (pinfunction "2_2") (pintype "bidirectional"))
      (node (ref "R27") (pin "1") (pinfunction "1_1") (pintype "passive"))
    )
    (net (code "118") (name "/PD15") (class "Default")
      (node (ref "IC7") (pin "13") (pinfunction "-IN_13") (pintype "input"))
      (node (ref "PHD15") (pin "2") (pinfunction "2_2") (pintype "bidirectional"))
      (node (ref "R35") (pin "1") (pinfunction "1_1") (pintype "passive"))
    )
    (net (code "119") (name "/PD16") (class "Default")
      (node (ref "IC7") (pin "9") (pinfunction "-IN_9") (pintype "input"))
      (node (ref "PHD16") (pin "2") (pinfunction "2_2") (pintype "bidirectional"))
      (node (ref "R26") (pin "1") (pinfunction "1_1") (pintype "passive"))
    )
    (net (code "120") (name "/PD17") (class "Default")
      (node (ref "IC17") (pin "2") (pinfunction "-IN_2") (pintype "input"))
      (node (ref "PHD17") (pin "2") (pinfunction "2_2") (pintype "bidirectional"))
      (node (ref "R66") (pin "1") (pinfunction "1_1") (pintype "passive"))
    )
    (net (code "121") (name "/PD18") (class "Default")
      (node (ref "IC17") (pin "6") (pinfunction "-IN_6") (pintype "input"))
      (node (ref "PHD18") (pin "2") (pinfunction "2_2") (pintype "bidirectional"))
      (node (ref "R77") (pin "1") (pinfunction "1_1") (pintype "passive"))
    )
    (net (code "122") (name "/PD19") (class "Default")
      (node (ref "IC20") (pin "2") (pinfunction "-IN_2") (pintype "input"))
      (node (ref "PHD19") (pin "2") (pinfunction "2_2") (pintype "bidirectional"))
      (node (ref "R70") (pin "1") (pinfunction "1_1") (pintype "passive"))
    )
    (net (code "123") (name "/PD20") (class "Default")
      (node (ref "IC20") (pin "6") (pinfunction "-IN_6") (pintype "input"))
      (node (ref "PHD20") (pin "2") (pinfunction "2_2") (pintype "bidirectional"))
      (node (ref "R80") (pin "1") (pinfunction "1_1") (pintype "passive"))
    )
    (net (code "124") (name "/PD21") (class "Default")
      (node (ref "IC2") (pin "2") (pinfunction "-IN_2") (pintype "input"))
      (node (ref "PHD21") (pin "2") (pinfunction "2_2") (pintype "bidirectional"))
      (node (ref "R5") (pin "1") (pinfunction "1_1") (pintype "passive"))
    )
    (net (code "125") (name "/PD22") (class "Default")
      (node (ref "IC2") (pin "6") (pinfunction "-IN_6") (pintype "input"))
      (node (ref "PHD22") (pin "2") (pinfunction "2_2") (pintype "bidirectional"))
      (node (ref "R18") (pin "1") (pinfunction "1_1") (pintype "passive"))
    )
    (net (code "126") (name "/PD23") (class "Default")
      (node (ref "IC1") (pin "2") (pinfunction "-IN_2") (pintype "input"))
      (node (ref "PHD23") (pin "2") (pinfunction "2_2") (pintype "bidirectional"))
      (node (ref "R4") (pin "1") (pinfunction "1_1") (pintype "passive"))
    )
    (net (code "127") (name "/PD24") (class "Default")
      (node (ref "IC1") (pin "6") (pinfunction "-IN_6") (pintype "input"))
      (node (ref "PHD24") (pin "2") (pinfunction "2_2") (pintype "bidirectional"))
      (node (ref "R15") (pin "1") (pinfunction "1_1") (pintype "passive"))
    )
    (net (code "128") (name "/PD25") (class "Default")
      (node (ref "IC17") (pin "13") (pinfunction "-IN_13") (pintype "input"))
      (node (ref "PHD25") (pin "2") (pinfunction "2_2") (pintype "bidirectional"))
      (node (ref "R90") (pin "1") (pinfunction "1_1") (pintype "passive"))
    )
    (net (code "129") (name "/PD26") (class "Default")
      (node (ref "IC17") (pin "9") (pinfunction "-IN_9") (pintype "input"))
      (node (ref "PHD26") (pin "2") (pinfunction "2_2") (pintype "bidirectional"))
      (node (ref "R83") (pin "1") (pinfunction "1_1") (pintype "passive"))
    )
    (net (code "130") (name "/PD27") (class "Default")
      (node (ref "IC20") (pin "13") (pinfunction "-IN_13") (pintype "input"))
      (node (ref "PHD27") (pin "2") (pinfunction "2_2") (pintype "bidirectional"))
      (node (ref "R96") (pin "1") (pinfunction "1_1") (pintype "passive"))
    )
    (net (code "131") (name "/PD28") (class "Default")
      (node (ref "IC20") (pin "9") (pinfunction "-IN_9") (pintype "input"))
      (node (ref "PHD28") (pin "2") (pinfunction "2_2") (pintype "bidirectional"))
      (node (ref "R87") (pin "1") (pinfunction "1_1") (pintype "passive"))
    )
    (net (code "132") (name "/PD29") (class "Default")
      (node (ref "IC2") (pin "13") (pinfunction "-IN_13") (pintype "input"))
      (node (ref "PHD29") (pin "2") (pinfunction "2_2") (pintype "bidirectional"))
      (node (ref "R41") (pin "1") (pinfunction "1_1") (pintype "passive"))
    )
    (net (code "133") (name "/PD30") (class "Default")
      (node (ref "IC2") (pin "9") (pinfunction "-IN_9") (pintype "input"))
      (node (ref "PHD30") (pin "2") (pinfunction "2_2") (pintype "bidirectional"))
      (node (ref "R24") (pin "1") (pinfunction "1_1") (pintype "passive"))
    )
    (net (code "134") (name "/PD31") (class "Default")
      (node (ref "IC1") (pin "13") (pinfunction "-IN_13") (pintype "input"))
      (node (ref "PHD31") (pin "2") (pinfunction "2_2") (pintype "bidirectional"))
      (node (ref "R44") (pin "1") (pinfunction "1_1") (pintype "passive"))
    )
    (net (code "135") (name "/PD32") (class "Default")
      (node (ref "IC1") (pin "9") (pinfunction "-IN_9") (pintype "input"))
      (node (ref "PHD32") (pin "2") (pinfunction "2_2") (pintype "bidirectional"))
      (node (ref "R25") (pin "1") (pinfunction "1_1") (pintype "passive"))
    )
    (net (code "136") (name "/PD33") (class "Default")
      (node (ref "IC13") (pin "2") (pinfunction "-IN_2") (pintype "input"))
      (node (ref "PHD33") (pin "2") (pinfunction "2_2") (pintype "bidirectional"))
      (node (ref "R49") (pin "1") (pinfunction "1_1") (pintype "passive"))
    )
    (net (code "137") (name "/PD34") (class "Default")
      (node (ref "IC13") (pin "6") (pinfunction "-IN_6") (pintype "input"))
      (node (ref "PHD34") (pin "2") (pinfunction "2_2") (pintype "bidirectional"))
      (node (ref "R55") (pin "1") (pinfunction "1_1") (pintype "passive"))
    )
    (net (code "138") (name "/PD35") (class "Default")
      (node (ref "IC12") (pin "2") (pinfunction "-IN_2") (pintype "input"))
      (node (ref "PHD35") (pin "2") (pinfunction "2_2") (pintype "bidirectional"))
      (node (ref "R48") (pin "1") (pinfunction "1_1") (pintype "passive"))
    )
    (net (code "139") (name "/PD36") (class "Default")
      (node (ref "IC12") (pin "6") (pinfunction "-IN_6") (pintype "input"))
      (node (ref "PHD36") (pin "2") (pinfunction "2_2") (pintype "bidirectional"))
      (node (ref "R54") (pin "1") (pinfunction "1_1") (pintype "passive"))
    )
    (net (code "140") (name "/PD37") (class "Default")
      (node (ref "IC23") (pin "2") (pinfunction "-IN_2") (pintype "input"))
      (node (ref "PHD37") (pin "2") (pinfunction "2_2") (pintype "bidirectional"))
      (node (ref "R72") (pin "1") (pinfunction "1_1") (pintype "passive"))
    )
    (net (code "141") (name "/PD38") (class "Default")
      (node (ref "IC23") (pin "6") (pinfunction "-IN_6") (pintype "input"))
      (node (ref "PHD38") (pin "2") (pinfunction "2_2") (pintype "bidirectional"))
      (node (ref "R76") (pin "1") (pinfunction "1_1") (pintype "passive"))
    )
    (net (code "142") (name "/PD39") (class "Default")
      (node (ref "IC19") (pin "2") (pinfunction "-IN_2") (pintype "input"))
      (node (ref "PHD39") (pin "2") (pinfunction "2_2") (pintype "bidirectional"))
      (node (ref "R71") (pin "1") (pinfunction "1_1") (pintype "passive"))
    )
    (net (code "143") (name "/PD40") (class "Default")
      (node (ref "IC19") (pin "6") (pinfunction "-IN_6") (pintype "input"))
      (node (ref "PHD40") (pin "2") (pinfunction "2_2") (pintype "bidirectional"))
      (node (ref "R75") (pin "1") (pinfunction "1_1") (pintype "passive"))
    )
    (net (code "144") (name "/PD41") (class "Default")
      (node (ref "IC13") (pin "13") (pinfunction "-IN_13") (pintype "input"))
      (node (ref "PHD41") (pin "2") (pinfunction "2_2") (pintype "bidirectional"))
      (node (ref "R65") (pin "1") (pinfunction "1_1") (pintype "passive"))
    )
    (net (code "145") (name "/PD42") (class "Default")
      (node (ref "IC13") (pin "9") (pinfunction "-IN_9") (pintype "input"))
      (node (ref "PHD42") (pin "2") (pinfunction "2_2") (pintype "bidirectional"))
      (node (ref "R60") (pin "1") (pinfunction "1_1") (pintype "passive"))
    )
    (net (code "146") (name "/PD43") (class "Default")
      (node (ref "IC12") (pin "13") (pinfunction "-IN_13") (pintype "input"))
      (node (ref "PHD43") (pin "2") (pinfunction "2_2") (pintype "bidirectional"))
      (node (ref "R64") (pin "1") (pinfunction "1_1") (pintype "passive"))
    )
    (net (code "147") (name "/PD44") (class "Default")
      (node (ref "IC12") (pin "9") (pinfunction "-IN_9") (pintype "input"))
      (node (ref "PHD44") (pin "2") (pinfunction "2_2") (pintype "bidirectional"))
      (node (ref "R59") (pin "1") (pinfunction "1_1") (pintype "passive"))
    )
    (net (code "148") (name "/PD45") (class "Default")
      (node (ref "IC23") (pin "13") (pinfunction "-IN_13") (pintype "input"))
      (node (ref "PHD45") (pin "2") (pinfunction "2_2") (pintype "bidirectional"))
      (node (ref "R94") (pin "1") (pinfunction "1_1") (pintype "passive"))
    )
    (net (code "149") (name "/PD46") (class "Default")
      (node (ref "IC23") (pin "9") (pinfunction "-IN_9") (pintype "input"))
      (node (ref "PHD46") (pin "2") (pinfunction "2_2") (pintype "bidirectional"))
      (node (ref "R82") (pin "1") (pinfunction "1_1") (pintype "passive"))
    )
    (net (code "150") (name "/PD47") (class "Default")
      (node (ref "IC19") (pin "13") (pinfunction "-IN_13") (pintype "input"))
      (node (ref "PHD47") (pin "2") (pinfunction "2_2") (pintype "bidirectional"))
      (node (ref "R92") (pin "1") (pinfunction "1_1") (pintype "passive"))
    )
    (net (code "151") (name "/PD48") (class "Default")
      (node (ref "IC19") (pin "9") (pinfunction "-IN_9") (pintype "input"))
      (node (ref "PHD48") (pin "2") (pinfunction "2_2") (pintype "bidirectional"))
      (node (ref "R86") (pin "1") (pinfunction "1_1") (pintype "passive"))
    )
    (net (code "152") (name "/PD49") (class "Default")
      (node (ref "IC6") (pin "2") (pinfunction "-IN_2") (pintype "input"))
      (node (ref "PHD49") (pin "2") (pinfunction "2_2") (pintype "bidirectional"))
      (node (ref "R1") (pin "1") (pinfunction "1_1") (pintype "passive"))
    )
    (net (code "153") (name "/PD50") (class "Default")
      (node (ref "IC6") (pin "6") (pinfunction "-IN_6") (pintype "input"))
      (node (ref "PHD50") (pin "2") (pinfunction "2_2") (pintype "bidirectional"))
      (node (ref "R14") (pin "1") (pinfunction "1_1") (pintype "passive"))
    )
    (net (code "154") (name "/PD51") (class "Default")
      (node (ref "IC16") (pin "2") (pinfunction "-IN_2") (pintype "input"))
      (node (ref "PHD51") (pin "2") (pinfunction "2_2") (pintype "bidirectional"))
      (node (ref "R47") (pin "1") (pinfunction "1_1") (pintype "passive"))
    )
    (net (code "155") (name "/PD52") (class "Default")
      (node (ref "IC16") (pin "6") (pinfunction "-IN_6") (pintype "input"))
      (node (ref "PHD52") (pin "2") (pinfunction "2_2") (pintype "bidirectional"))
      (node (ref "R51") (pin "1") (pinfunction "1_1") (pintype "passive"))
    )
    (net (code "156") (name "/PD53") (class "Default")
      (node (ref "IC18") (pin "2") (pinfunction "-IN_2") (pintype "input"))
      (node (ref "PHD53") (pin "2") (pinfunction "2_2") (pintype "bidirectional"))
      (node (ref "R69") (pin "1") (pinfunction "1_1") (pintype "passive"))
    )
    (net (code "157") (name "/PD54") (class "Default")
      (node (ref "IC18") (pin "6") (pinfunction "-IN_6") (pintype "input"))
      (node (ref "PHD54") (pin "2") (pinfunction "2_2") (pintype "bidirectional"))
      (node (ref "R74") (pin "1") (pinfunction "1_1") (pintype "passive"))
    )
    (net (code "158") (name "/PD55") (class "Default")
      (node (ref "IC4") (pin "2") (pinfunction "-IN_2") (pintype "input"))
      (node (ref "PHD55") (pin "2") (pinfunction "2_2") (pintype "bidirectional"))
      (node (ref "R3") (pin "1") (pinfunction "1_1") (pintype "passive"))
    )
    (net (code "159") (name "/PD56") (class "Default")
      (node (ref "IC4") (pin "6") (pinfunction "-IN_6") (pintype "input"))
      (node (ref "PHD56") (pin "2") (pinfunction "2_2") (pintype "bidirectional"))
      (node (ref "R16") (pin "1") (pinfunction "1_1") (pintype "passive"))
    )
    (net (code "160") (name "/PD57") (class "Default")
      (node (ref "IC6") (pin "13") (pinfunction "-IN_13") (pintype "input"))
      (node (ref "PHD57") (pin "2") (pinfunction "2_2") (pintype "bidirectional"))
      (node (ref "R42") (pin "1") (pinfunction "1_1") (pintype "passive"))
    )
    (net (code "161") (name "/PD58") (class "Default")
      (node (ref "IC6") (pin "9") (pinfunction "-IN_9") (pintype "input"))
      (node (ref "PHD58") (pin "2") (pinfunction "2_2") (pintype "bidirectional"))
      (node (ref "R29") (pin "1") (pinfunction "1_1") (pintype "passive"))
    )
    (net (code "162") (name "/PD59") (class "Default")
      (node (ref "IC16") (pin "13") (pinfunction "-IN_13") (pintype "input"))
      (node (ref "PHD59") (pin "2") (pinfunction "2_2") (pintype "bidirectional"))
      (node (ref "R61") (pin "1") (pinfunction "1_1") (pintype "passive"))
    )
    (net (code "163") (name "/PD60") (class "Default")
      (node (ref "IC16") (pin "9") (pinfunction "-IN_9") (pintype "input"))
      (node (ref "PHD60") (pin "2") (pinfunction "2_2") (pintype "bidirectional"))
      (node (ref "R57") (pin "1") (pinfunction "1_1") (pintype "passive"))
    )
    (net (code "164") (name "/PD61") (class "Default")
      (node (ref "IC18") (pin "13") (pinfunction "-IN_13") (pintype "input"))
      (node (ref "PHD61") (pin "2") (pinfunction "2_2") (pintype "bidirectional"))
      (node (ref "R91") (pin "1") (pinfunction "1_1") (pintype "passive"))
    )
    (net (code "165") (name "/PD62") (class "Default")
      (node (ref "IC18") (pin "9") (pinfunction "-IN_9") (pintype "input"))
      (node (ref "PHD62") (pin "2") (pinfunction "2_2") (pintype "bidirectional"))
      (node (ref "R85") (pin "1") (pinfunction "1_1") (pintype "passive"))
    )
    (net (code "166") (name "/PD63") (class "Default")
      (node (ref "IC4") (pin "13") (pinfunction "-IN_13") (pintype "input"))
      (node (ref "PHD63") (pin "2") (pinfunction "2_2") (pintype "bidirectional"))
      (node (ref "R40") (pin "1") (pinfunction "1_1") (pintype "passive"))
    )
    (net (code "167") (name "/PD64") (class "Default")
      (node (ref "IC4") (pin "9") (pinfunction "-IN_9") (pintype "input"))
      (node (ref "PHD64") (pin "2") (pinfunction "2_2") (pintype "bidirectional"))
      (node (ref "R32") (pin "1") (pinfunction "1_1") (pintype "passive"))
    )
    (net (code "168") (name "/PD65") (class "Default")
      (node (ref "IC14") (pin "2") (pinfunction "-IN_2") (pintype "input"))
      (node (ref "PHD65") (pin "2") (pinfunction "2_2") (pintype "bidirectional"))
      (node (ref "R46") (pin "1") (pinfunction "1_1") (pintype "passive"))
    )
    (net (code "169") (name "/PD66") (class "Default")
      (node (ref "IC14") (pin "6") (pinfunction "-IN_6") (pintype "input"))
      (node (ref "PHD66") (pin "2") (pinfunction "2_2") (pintype "bidirectional"))
      (node (ref "R52") (pin "1") (pinfunction "1_1") (pintype "passive"))
    )
    (net (code "170") (name "/PD67") (class "Default")
      (node (ref "IC24") (pin "2") (pinfunction "-IN_2") (pintype "input"))
      (node (ref "PHD67") (pin "2") (pinfunction "2_2") (pintype "bidirectional"))
      (node (ref "R67") (pin "1") (pinfunction "1_1") (pintype "passive"))
    )
    (net (code "171") (name "/PD68") (class "Default")
      (node (ref "IC24") (pin "6") (pinfunction "-IN_6") (pintype "input"))
      (node (ref "PHD68") (pin "2") (pinfunction "2_2") (pintype "bidirectional"))
      (node (ref "R78") (pin "1") (pinfunction "1_1") (pintype "passive"))
    )
    (net (code "172") (name "/PD69") (class "Default")
      (node (ref "IC5") (pin "2") (pinfunction "-IN_2") (pintype "input"))
      (node (ref "PHD69") (pin "2") (pinfunction "2_2") (pintype "bidirectional"))
      (node (ref "R7") (pin "1") (pinfunction "1_1") (pintype "passive"))
    )
    (net (code "173") (name "/PD70") (class "Default")
      (node (ref "IC5") (pin "6") (pinfunction "-IN_6") (pintype "input"))
      (node (ref "PHD70") (pin "2") (pinfunction "2_2") (pintype "bidirectional"))
      (node (ref "R13") (pin "1") (pinfunction "1_1") (pintype "passive"))
    )
    (net (code "174") (name "/PD71") (class "Default")
      (node (ref "IC15") (pin "2") (pinfunction "-IN_2") (pintype "input"))
      (node (ref "PHD71") (pin "2") (pinfunction "2_2") (pintype "bidirectional"))
      (node (ref "R50") (pin "1") (pinfunction "1_1") (pintype "passive"))
    )
    (net (code "175") (name "/PD72") (class "Default")
      (node (ref "IC15") (pin "6") (pinfunction "-IN_6") (pintype "input"))
      (node (ref "PHD72") (pin "2") (pinfunction "2_2") (pintype "bidirectional"))
      (node (ref "R53") (pin "1") (pinfunction "1_1") (pintype "passive"))
    )
    (net (code "176") (name "/PD73") (class "Default")
      (node (ref "IC14") (pin "13") (pinfunction "-IN_13") (pintype "input"))
      (node (ref "PHD73") (pin "2") (pinfunction "2_2") (pintype "bidirectional"))
      (node (ref "R62") (pin "1") (pinfunction "1_1") (pintype "passive"))
    )
    (net (code "177") (name "/PD74") (class "Default")
      (node (ref "IC14") (pin "9") (pinfunction "-IN_9") (pintype "input"))
      (node (ref "PHD74") (pin "2") (pinfunction "2_2") (pintype "bidirectional"))
      (node (ref "R58") (pin "1") (pinfunction "1_1") (pintype "passive"))
    )
    (net (code "178") (name "/PD75") (class "Default")
      (node (ref "IC24") (pin "13") (pinfunction "-IN_13") (pintype "input"))
      (node (ref "PHD75") (pin "2") (pinfunction "2_2") (pintype "bidirectional"))
      (node (ref "R95") (pin "1") (pinfunction "1_1") (pintype "passive"))
    )
    (net (code "179") (name "/PD76") (class "Default")
      (node (ref "IC24") (pin "9") (pinfunction "-IN_9") (pintype "input"))
      (node (ref "PHD76") (pin "2") (pinfunction "2_2") (pintype "bidirectional"))
      (node (ref "R84") (pin "1") (pinfunction "1_1") (pintype "passive"))
    )
    (net (code "180") (name "/PD77") (class "Default")
      (node (ref "IC5") (pin "13") (pinfunction "-IN_13") (pintype "input"))
      (node (ref "PHD77") (pin "2") (pinfunction "2_2") (pintype "bidirectional"))
      (node (ref "R43") (pin "1") (pinfunction "1_1") (pintype "passive"))
    )
    (net (code "181") (name "/PD78") (class "Default")
      (node (ref "IC5") (pin "9") (pinfunction "-IN_9") (pintype "input"))
      (node (ref "PHD78") (pin "2") (pinfunction "2_2") (pintype "bidirectional"))
      (node (ref "R33") (pin "1") (pinfunction "1_1") (pintype "passive"))
    )
    (net (code "182") (name "/PD79") (class "Default")
      (node (ref "IC15") (pin "13") (pinfunction "-IN_13") (pintype "input"))
      (node (ref "PHD79") (pin "2") (pinfunction "2_2") (pintype "bidirectional"))
      (node (ref "R63") (pin "1") (pinfunction "1_1") (pintype "passive"))
    )
    (net (code "183") (name "/PD80") (class "Default")
      (node (ref "IC15") (pin "9") (pinfunction "-IN_9") (pintype "input"))
      (node (ref "PHD80") (pin "2") (pinfunction "2_2") (pintype "bidirectional"))
      (node (ref "R56") (pin "1") (pinfunction "1_1") (pintype "passive"))
    )
    (net (code "184") (name "/PD81") (class "Default")
      (node (ref "IC22") (pin "2") (pinfunction "-IN_2") (pintype "input"))
      (node (ref "PHD81") (pin "2") (pinfunction "2_2") (pintype "bidirectional"))
      (node (ref "R68") (pin "1") (pinfunction "1_1") (pintype "passive"))
    )
    (net (code "185") (name "/PD82") (class "Default")
      (node (ref "IC22") (pin "6") (pinfunction "-IN_6") (pintype "input"))
      (node (ref "PHD82") (pin "2") (pinfunction "2_2") (pintype "bidirectional"))
      (node (ref "R79") (pin "1") (pinfunction "1_1") (pintype "passive"))
    )
    (net (code "186") (name "/PD83") (class "Default")
      (node (ref "IC3") (pin "2") (pinfunction "-IN_2") (pintype "input"))
      (node (ref "PHD83") (pin "2") (pinfunction "2_2") (pintype "bidirectional"))
      (node (ref "R2") (pin "1") (pinfunction "1_1") (pintype "passive"))
    )
    (net (code "187") (name "/PD84") (class "Default")
      (node (ref "IC3") (pin "6") (pinfunction "-IN_6") (pintype "input"))
      (node (ref "PHD84") (pin "2") (pinfunction "2_2") (pintype "bidirectional"))
      (node (ref "R17") (pin "1") (pinfunction "1_1") (pintype "passive"))
    )
    (net (code "188") (name "/PD85") (class "Default")
      (node (ref "IC9") (pin "2") (pinfunction "-IN_2") (pintype "input"))
      (node (ref "PHD85") (pin "2") (pinfunction "2_2") (pintype "bidirectional"))
      (node (ref "R10") (pin "1") (pinfunction "1_1") (pintype "passive"))
    )
    (net (code "189") (name "/PD86") (class "Default")
      (node (ref "IC9") (pin "6") (pinfunction "-IN_6") (pintype "input"))
      (node (ref "PHD86") (pin "2") (pinfunction "2_2") (pintype "bidirectional"))
      (node (ref "R21") (pin "1") (pinfunction "1_1") (pintype "passive"))
    )
    (net (code "190") (name "/PD87") (class "Default")
      (node (ref "IC21") (pin "2") (pinfunction "-IN_2") (pintype "input"))
      (node (ref "PHD87") (pin "2") (pinfunction "2_2") (pintype "bidirectional"))
      (node (ref "R73") (pin "1") (pinfunction "1_1") (pintype "passive"))
    )
    (net (code "191") (name "/PD88") (class "Default")
      (node (ref "IC21") (pin "6") (pinfunction "-IN_6") (pintype "input"))
      (node (ref "PHD88") (pin "2") (pinfunction "2_2") (pintype "bidirectional"))
      (node (ref "R81") (pin "1") (pinfunction "1_1") (pintype "passive"))
    )
    (net (code "192") (name "/PD89") (class "Default")
      (node (ref "IC22") (pin "13") (pinfunction "-IN_13") (pintype "input"))
      (node (ref "PHD89") (pin "2") (pinfunction "2_2") (pintype "bidirectional"))
      (node (ref "R93") (pin "1") (pinfunction "1_1") (pintype "passive"))
    )
    (net (code "193") (name "/PD90") (class "Default")
      (node (ref "IC22") (pin "9") (pinfunction "-IN_9") (pintype "input"))
      (node (ref "PHD90") (pin "2") (pinfunction "2_2") (pintype "bidirectional"))
      (node (ref "R88") (pin "1") (pinfunction "1_1") (pintype "passive"))
    )
    (net (code "194") (name "/PD91") (class "Default")
      (node (ref "IC3") (pin "13") (pinfunction "-IN_13") (pintype "input"))
      (node (ref "PHD91") (pin "2") (pinfunction "2_2") (pintype "bidirectional"))
      (node (ref "R45") (pin "1") (pinfunction "1_1") (pintype "passive"))
    )
    (net (code "195") (name "/PD92") (class "Default")
      (node (ref "IC3") (pin "9") (pinfunction "-IN_9") (pintype "input"))
      (node (ref "PHD92") (pin "2") (pinfunction "2_2") (pintype "bidirectional"))
      (node (ref "R34") (pin "1") (pinfunction "1_1") (pintype "passive"))
    )
    (net (code "196") (name "/PD93") (class "Default")
      (node (ref "IC9") (pin "13") (pinfunction "-IN_13") (pintype "input"))
      (node (ref "PHD93") (pin "2") (pinfunction "2_2") (pintype "bidirectional"))
      (node (ref "R37") (pin "1") (pinfunction "1_1") (pintype "passive"))
    )
    (net (code "197") (name "/PD94") (class "Default")
      (node (ref "IC9") (pin "9") (pinfunction "-IN_9") (pintype "input"))
      (node (ref "PHD94") (pin "2") (pinfunction "2_2") (pintype "bidirectional"))
      (node (ref "R28") (pin "1") (pinfunction "1_1") (pintype "passive"))
    )
    (net (code "198") (name "/PD95") (class "Default")
      (node (ref "IC21") (pin "13") (pinfunction "-IN_13") (pintype "input"))
      (node (ref "PHD95") (pin "2") (pinfunction "2_2") (pintype "bidirectional"))
      (node (ref "R97") (pin "1") (pinfunction "1_1") (pintype "passive"))
    )
    (net (code "199") (name "/PD96") (class "Default")
      (node (ref "IC21") (pin "9") (pinfunction "-IN_9") (pintype "input"))
      (node (ref "PHD96") (pin "2") (pinfunction "2_2") (pintype "bidirectional"))
      (node (ref "R89") (pin "1") (pinfunction "1_1") (pintype "passive"))
    )
    (net (code "200") (name "/S0") (class "Default")
      (node (ref "J2") (pin "1") (pinfunction "1_1") (pintype "passive"))
      (node (ref "U1") (pin "10") (pinfunction "SEL0_10") (pintype "bidirectional"))
      (node (ref "U2") (pin "10") (pinfunction "SEL0_10") (pintype "bidirectional"))
      (node (ref "U3") (pin "10") (pinfunction "SEL0_10") (pintype "bidirectional"))
      (node (ref "U4") (pin "10") (pinfunction "SEL0_10") (pintype "bidirectional"))
      (node (ref "U5") (pin "10") (pinfunction "SEL0_10") (pintype "bidirectional"))
      (node (ref "U6") (pin "10") (pinfunction "SEL0_10") (pintype "bidirectional"))
    )
    (net (code "201") (name "/S1") (class "Default")
      (node (ref "J2") (pin "2") (pinfunction "2_2") (pintype "passive"))
      (node (ref "U1") (pin "11") (pinfunction "SEL1_11") (pintype "bidirectional"))
      (node (ref "U2") (pin "11") (pinfunction "SEL1_11") (pintype "bidirectional"))
      (node (ref "U3") (pin "11") (pinfunction "SEL1_11") (pintype "bidirectional"))
      (node (ref "U4") (pin "11") (pinfunction "SEL1_11") (pintype "bidirectional"))
      (node (ref "U5") (pin "11") (pinfunction "SEL1_11") (pintype "bidirectional"))
      (node (ref "U6") (pin "11") (pinfunction "SEL1_11") (pintype "bidirectional"))
    )
    (net (code "202") (name "/S2") (class "Default")
      (node (ref "J2") (pin "3") (pinfunction "3_3") (pintype "passive"))
      (node (ref "U1") (pin "14") (pinfunction "SEL2_14") (pintype "bidirectional"))
      (node (ref "U2") (pin "14") (pinfunction "SEL2_14") (pintype "bidirectional"))
      (node (ref "U3") (pin "14") (pinfunction "SEL2_14") (pintype "bidirectional"))
      (node (ref "U4") (pin "14") (pinfunction "SEL2_14") (pintype "bidirectional"))
      (node (ref "U5") (pin "14") (pinfunction "SEL2_14") (pintype "bidirectional"))
      (node (ref "U6") (pin "14") (pinfunction "SEL2_14") (pintype "bidirectional"))
    )
    (net (code "203") (name "/S3") (class "Default")
      (node (ref "J2") (pin "4") (pinfunction "4_4") (pintype "passive"))
      (node (ref "U1") (pin "13") (pinfunction "SEL3_13") (pintype "bidirectional"))
      (node (ref "U2") (pin "13") (pinfunction "SEL3_13") (pintype "bidirectional"))
      (node (ref "U3") (pin "13") (pinfunction "SEL3_13") (pintype "bidirectional"))
      (node (ref "U4") (pin "13") (pinfunction "SEL3_13") (pintype "bidirectional"))
      (node (ref "U5") (pin "13") (pinfunction "SEL3_13") (pintype "bidirectional"))
      (node (ref "U6") (pin "13") (pinfunction "SEL3_13") (pintype "bidirectional"))
    )
    (net (code "204") (name "GND") (class "Default")
      (node (ref "C1") (pin "2") (pinfunction "2_2") (pintype "passive"))
      (node (ref "C10") (pin "2") (pinfunction "2_2") (pintype "passive"))
      (node (ref "C11") (pin "2") (pinfunction "2_2") (pintype "passive"))
      (node (ref "C12") (pin "2") (pinfunction "2_2") (pintype "passive"))
      (node (ref "C13") (pin "2") (pinfunction "2_2") (pintype "passive"))
      (node (ref "C14") (pin "2") (pinfunction "2_2") (pintype "passive"))
      (node (ref "C15") (pin "2") (pinfunction "2_2") (pintype "passive"))
      (node (ref "C16") (pin "2") (pinfunction "2_2") (pintype "passive"))
      (node (ref "C17") (pin "2") (pinfunction "2_2") (pintype "passive"))
      (node (ref "C18") (pin "2") (pinfunction "2_2") (pintype "passive"))
      (node (ref "C19") (pin "2") (pinfunction "2_2") (pintype "passive"))
      (node (ref "C2") (pin "2") (pinfunction "2_2") (pintype "passive"))
      (node (ref "C20") (pin "2") (pinfunction "2_2") (pintype "passive"))
      (node (ref "C21") (pin "2") (pinfunction "2_2") (pintype "passive"))
      (node (ref "C22") (pin "2") (pinfunction "2_2") (pintype "passive"))
      (node (ref "C23") (pin "2") (pinfunction "2_2") (pintype "passive"))
      (node (ref "C25") (pin "2") (pinfunction "2_2") (pintype "passive"))
      (node (ref "C3") (pin "2") (pinfunction "2_2") (pintype "passive"))
      (node (ref "C4") (pin "2") (pinfunction "2_2") (pintype "passive"))
      (node (ref "C5") (pin "2") (pinfunction "2_2") (pintype "passive"))
      (node (ref "C6") (pin "2") (pinfunction "2_2") (pintype "passive"))
      (node (ref "C7") (pin "2") (pinfunction "2_2") (pintype "passive"))
      (node (ref "C8") (pin "2") (pinfunction "2_2") (pintype "passive"))
      (node (ref "C9") (pin "2") (pinfunction "2_2") (pintype "passive"))
      (node (ref "IC1") (pin "10") (pinfunction "+IN_10") (pintype "input"))
      (node (ref "IC1") (pin "11") (pinfunction "V-_11") (pintype "power_in"))
      (node (ref "IC1") (pin "12") (pinfunction "+IN_12") (pintype "input"))
      (node (ref "IC1") (pin "3") (pinfunction "+IN_3") (pintype "input"))
      (node (ref "IC1") (pin "5") (pinfunction "+IN_5") (pintype "input"))
      (node (ref "IC10") (pin "10") (pinfunction "+IN_10") (pintype "input"))
      (node (ref "IC10") (pin "11") (pinfunction "V-_11") (pintype "power_in"))
      (node (ref "IC10") (pin "12") (pinfunction "+IN_12") (pintype "input"))
      (node (ref "IC10") (pin "3") (pinfunction "+IN_3") (pintype "input"))
      (node (ref "IC10") (pin "5") (pinfunction "+IN_5") (pintype "input"))
      (node (ref "IC11") (pin "10") (pinfunction "+IN_10") (pintype "input"))
      (node (ref "IC11") (pin "11") (pinfunction "V-_11") (pintype "power_in"))
      (node (ref "IC11") (pin "12") (pinfunction "+IN_12") (pintype "input"))
      (node (ref "IC11") (pin "3") (pinfunction "+IN_3") (pintype "input"))
      (node (ref "IC11") (pin "5") (pinfunction "+IN_5") (pintype "input"))
      (node (ref "IC12") (pin "10") (pinfunction "+IN_10") (pintype "input"))
      (node (ref "IC12") (pin "11") (pinfunction "V-_11") (pintype "power_in"))
      (node (ref "IC12") (pin "12") (pinfunction "+IN_12") (pintype "input"))
      (node (ref "IC12") (pin "3") (pinfunction "+IN_3") (pintype "input"))
      (node (ref "IC12") (pin "5") (pinfunction "+IN_5") (pintype "input"))
      (node (ref "IC13") (pin "10") (pinfunction "+IN_10") (pintype "input"))
      (node (ref "IC13") (pin "11") (pinfunction "V-_11") (pintype "power_in"))
      (node (ref "IC13") (pin "12") (pinfunction "+IN_12") (pintype "input"))
      (node (ref "IC13") (pin "3") (pinfunction "+IN_3") (pintype "input"))
      (node (ref "IC13") (pin "5") (pinfunction "+IN_5") (pintype "input"))
      (node (ref "IC14") (pin "10") (pinfunction "+IN_10") (pintype "input"))
      (node (ref "IC14") (pin "11") (pinfunction "V-_11") (pintype "power_in"))
      (node (ref "IC14") (pin "12") (pinfunction "+IN_12") (pintype "input"))
      (node (ref "IC14") (pin "3") (pinfunction "+IN_3") (pintype "input"))
      (node (ref "IC14") (pin "5") (pinfunction "+IN_5") (pintype "input"))
      (node (ref "IC15") (pin "10") (pinfunction "+IN_10") (pintype "input"))
      (node (ref "IC15") (pin "11") (pinfunction "V-_11") (pintype "power_in"))
      (node (ref "IC15") (pin "12") (pinfunction "+IN_12") (pintype "input"))
      (node (ref "IC15") (pin "3") (pinfunction "+IN_3") (pintype "input"))
      (node (ref "IC15") (pin "5") (pinfunction "+IN_5") (pintype "input"))
      (node (ref "IC16") (pin "10") (pinfunction "+IN_10") (pintype "input"))
      (node (ref "IC16") (pin "11") (pinfunction "V-_11") (pintype "power_in"))
      (node (ref "IC16") (pin "12") (pinfunction "+IN_12") (pintype "input"))
      (node (ref "IC16") (pin "3") (pinfunction "+IN_3") (pintype "input"))
      (node (ref "IC16") (pin "5") (pinfunction "+IN_5") (pintype "input"))
      (node (ref "IC17") (pin "10") (pinfunction "+IN_10") (pintype "input"))
      (node (ref "IC17") (pin "11") (pinfunction "V-_11") (pintype "power_in"))
      (node (ref "IC17") (pin "12") (pinfunction "+IN_12") (pintype "input"))
      (node (ref "IC17") (pin "3") (pinfunction "+IN_3") (pintype "input"))
      (node (ref "IC17") (pin "5") (pinfunction "+IN_5") (pintype "input"))
      (node (ref "IC18") (pin "10") (pinfunction "+IN_10") (pintype "input"))
      (node (ref "IC18") (pin "11") (pinfunction "V-_11") (pintype "power_in"))
      (node (ref "IC18") (pin "12") (pinfunction "+IN_12") (pintype "input"))
      (node (ref "IC18") (pin "3") (pinfunction "+IN_3") (pintype "input"))
      (node (ref "IC18") (pin "5") (pinfunction "+IN_5") (pintype "input"))
      (node (ref "IC19") (pin "10") (pinfunction "+IN_10") (pintype "input"))
      (node (ref "IC19") (pin "11") (pinfunction "V-_11") (pintype "power_in"))
      (node (ref "IC19") (pin "12") (pinfunction "+IN_12") (pintype "input"))
      (node (ref "IC19") (pin "3") (pinfunction "+IN_3") (pintype "input"))
      (node (ref "IC19") (pin "5") (pinfunction "+IN_5") (pintype "input"))
      (node (ref "IC2") (pin "10") (pinfunction "+IN_10") (pintype "input"))
      (node (ref "IC2") (pin "11") (pinfunction "V-_11") (pintype "power_in"))
      (node (ref "IC2") (pin "12") (pinfunction "+IN_12") (pintype "input"))
      (node (ref "IC2") (pin "3") (pinfunction "+IN_3") (pintype "input"))
      (node (ref "IC2") (pin "5") (pinfunction "+IN_5") (pintype "input"))
      (node (ref "IC20") (pin "10") (pinfunction "+IN_10") (pintype "input"))
      (node (ref "IC20") (pin "11") (pinfunction "V-_11") (pintype "power_in"))
      (node (ref "IC20") (pin "12") (pinfunction "+IN_12") (pintype "input"))
      (node (ref "IC20") (pin "3") (pinfunction "+IN_3") (pintype "input"))
      (node (ref "IC20") (pin "5") (pinfunction "+IN_5") (pintype "input"))
      (node (ref "IC21") (pin "10") (pinfunction "+IN_10") (pintype "input"))
      (node (ref "IC21") (pin "11") (pinfunction "V-_11") (pintype "power_in"))
      (node (ref "IC21") (pin "12") (pinfunction "+IN_12") (pintype "input"))
      (node (ref "IC21") (pin "3") (pinfunction "+IN_3") (pintype "input"))
      (node (ref "IC21") (pin "5") (pinfunction "+IN_5") (pintype "input"))
      (node (ref "IC22") (pin "10") (pinfunction "+IN_10") (pintype "input"))
      (node (ref "IC22") (pin "11") (pinfunction "V-_11") (pintype "power_in"))
      (node (ref "IC22") (pin "12") (pinfunction "+IN_12") (pintype "input"))
      (node (ref "IC22") (pin "3") (pinfunction "+IN_3") (pintype "input"))
      (node (ref "IC22") (pin "5") (pinfunction "+IN_5") (pintype "input"))
      (node (ref "IC23") (pin "10") (pinfunction "+IN_10") (pintype "input"))
      (node (ref "IC23") (pin "11") (pinfunction "V-_11") (pintype "power_in"))
      (node (ref "IC23") (pin "12") (pinfunction "+IN_12") (pintype "input"))
      (node (ref "IC23") (pin "3") (pinfunction "+IN_3") (pintype "input"))
      (node (ref "IC23") (pin "5") (pinfunction "+IN_5") (pintype "input"))
      (node (ref "IC24") (pin "10") (pinfunction "+IN_10") (pintype "input"))
      (node (ref "IC24") (pin "11") (pinfunction "V-_11") (pintype "power_in"))
      (node (ref "IC24") (pin "12") (pinfunction "+IN_12") (pintype "input"))
      (node (ref "IC24") (pin "3") (pinfunction "+IN_3") (pintype "input"))
      (node (ref "IC24") (pin "5") (pinfunction "+IN_5") (pintype "input"))
      (node (ref "IC3") (pin "10") (pinfunction "+IN_10") (pintype "input"))
      (node (ref "IC3") (pin "11") (pinfunction "V-_11") (pintype "power_in"))
      (node (ref "IC3") (pin "12") (pinfunction "+IN_12") (pintype "input"))
      (node (ref "IC3") (pin "3") (pinfunction "+IN_3") (pintype "input"))
      (node (ref "IC3") (pin "5") (pinfunction "+IN_5") (pintype "input"))
      (node (ref "IC4") (pin "10") (pinfunction "+IN_10") (pintype "input"))
      (node (ref "IC4") (pin "11") (pinfunction "V-_11") (pintype "power_in"))
      (node (ref "IC4") (pin "12") (pinfunction "+IN_12") (pintype "input"))
      (node (ref "IC4") (pin "3") (pinfunction "+IN_3") (pintype "input"))
      (node (ref "IC4") (pin "5") (pinfunction "+IN_5") (pintype "input"))
      (node (ref "IC5") (pin "10") (pinfunction "+IN_10") (pintype "input"))
      (node (ref "IC5") (pin "11") (pinfunction "V-_11") (pintype "power_in"))
      (node (ref "IC5") (pin "12") (pinfunction "+IN_12") (pintype "input"))
      (node (ref "IC5") (pin "3") (pinfunction "+IN_3") (pintype "input"))
      (node (ref "IC5") (pin "5") (pinfunction "+IN_5") (pintype "input"))
      (node (ref "IC6") (pin "10") (pinfunction "+IN_10") (pintype "input"))
      (node (ref "IC6") (pin "11") (pinfunction "V-_11") (pintype "power_in"))
      (node (ref "IC6") (pin "12") (pinfunction "+IN_12") (pintype "input"))
      (node (ref "IC6") (pin "3") (pinfunction "+IN_3") (pintype "input"))
      (node (ref "IC6") (pin "5") (pinfunction "+IN_5") (pintype "input"))
      (node (ref "IC7") (pin "10") (pinfunction "+IN_10") (pintype "input"))
      (node (ref "IC7") (pin "11") (pinfunction "V-_11") (pintype "power_in"))
      (node (ref "IC7") (pin "12") (pinfunction "+IN_12") (pintype "input"))
      (node (ref "IC7") (pin "3") (pinfunction "+IN_3") (pintype "input"))
      (node (ref "IC7") (pin "5") (pinfunction "+IN_5") (pintype "input"))
      (node (ref "IC8") (pin "10") (pinfunction "+IN_10") (pintype "input"))
      (node (ref "IC8") (pin "11") (pinfunction "V-_11") (pintype "power_in"))
      (node (ref "IC8") (pin "12") (pinfunction "+IN_12") (pintype "input"))
      (node (ref "IC8") (pin "3") (pinfunction "+IN_3") (pintype "input"))
      (node (ref "IC8") (pin "5") (pinfunction "+IN_5") (pintype "input"))
      (node (ref "IC9") (pin "10") (pinfunction "+IN_10") (pintype "input"))
      (node (ref "IC9") (pin "11") (pinfunction "V-_11") (pintype "power_in"))
      (node (ref "IC9") (pin "12") (pinfunction "+IN_12") (pintype "input"))
      (node (ref "IC9") (pin "3") (pinfunction "+IN_3") (pintype "input"))
      (node (ref "IC9") (pin "5") (pinfunction "+IN_5") (pintype "input"))
      (node (ref "J2") (pin "5") (pinfunction "5_5") (pintype "passive"))
      (node (ref "PHD1") (pin "1") (pinfunction "1_1") (pintype "bidirectional"))
      (node (ref "PHD10") (pin "1") (pinfunction "1_1") (pintype "bidirectional"))
      (node (ref "PHD11") (pin "1") (pinfunction "1_1") (pintype "bidirectional"))
      (node (ref "PHD12") (pin "1") (pinfunction "1_1") (pintype "bidirectional"))
      (node (ref "PHD13") (pin "1") (pinfunction "1_1") (pintype "bidirectional"))
      (node (ref "PHD14") (pin "1") (pinfunction "1_1") (pintype "bidirectional"))
      (node (ref "PHD15") (pin "1") (pinfunction "1_1") (pintype "bidirectional"))
      (node (ref "PHD16") (pin "1") (pinfunction "1_1") (pintype "bidirectional"))
      (node (ref "PHD17") (pin "1") (pinfunction "1_1") (pintype "bidirectional"))
      (node (ref "PHD18") (pin "1") (pinfunction "1_1") (pintype "bidirectional"))
      (node (ref "PHD19") (pin "1") (pinfunction "1_1") (pintype "bidirectional"))
      (node (ref "PHD2") (pin "1") (pinfunction "1_1") (pintype "bidirectional"))
      (node (ref "PHD20") (pin "1") (pinfunction "1_1") (pintype "bidirectional"))
      (node (ref "PHD21") (pin "1") (pinfunction "1_1") (pintype "bidirectional"))
      (node (ref "PHD22") (pin "1") (pinfunction "1_1") (pintype "bidirectional"))
      (node (ref "PHD23") (pin "1") (pinfunction "1_1") (pintype "bidirectional"))
      (node (ref "PHD24") (pin "1") (pinfunction "1_1") (pintype "bidirectional"))
      (node (ref "PHD25") (pin "1") (pinfunction "1_1") (pintype "bidirectional"))
      (node (ref "PHD26") (pin "1") (pinfunction "1_1") (pintype "bidirectional"))
      (node (ref "PHD27") (pin "1") (pinfunction "1_1") (pintype "bidirectional"))
      (node (ref "PHD28") (pin "1") (pinfunction "1_1") (pintype "bidirectional"))
      (node (ref "PHD29") (pin "1") (pinfunction "1_1") (pintype "bidirectional"))
      (node (ref "PHD3") (pin "1") (pinfunction "1_1") (pintype "bidirectional"))
      (node (ref "PHD30") (pin "1") (pinfunction "1_1") (pintype "bidirectional"))
      (node (ref "PHD31") (pin "1") (pinfunction "1_1") (pintype "bidirectional"))
      (node (ref "PHD32") (pin "1") (pinfunction "1_1") (pintype "bidirectional"))
      (node (ref "PHD33") (pin "1") (pinfunction "1_1") (pintype "bidirectional"))
      (node (ref "PHD34") (pin "1") (pinfunction "1_1") (pintype "bidirectional"))
      (node (ref "PHD35") (pin "1") (pinfunction "1_1") (pintype "bidirectional"))
      (node (ref "PHD36") (pin "1") (pinfunction "1_1") (pintype "bidirectional"))
      (node (ref "PHD37") (pin "1") (pinfunction "1_1") (pintype "bidirectional"))
      (node (ref "PHD38") (pin "1") (pinfunction "1_1") (pintype "bidirectional"))
      (node (ref "PHD39") (pin "1") (pinfunction "1_1") (pintype "bidirectional"))
      (node (ref "PHD4") (pin "1") (pinfunction "1_1") (pintype "bidirectional"))
      (node (ref "PHD40") (pin "1") (pinfunction "1_1") (pintype "bidirectional"))
      (node (ref "PHD41") (pin "1") (pinfunction "1_1") (pintype "bidirectional"))
      (node (ref "PHD42") (pin "1") (pinfunction "1_1") (pintype "bidirectional"))
      (node (ref "PHD43") (pin "1") (pinfunction "1_1") (pintype "bidirectional"))
      (node (ref "PHD44") (pin "1") (pinfunction "1_1") (pintype "bidirectional"))
      (node (ref "PHD45") (pin "1") (pinfunction "1_1") (pintype "bidirectional"))
      (node (ref "PHD46") (pin "1") (pinfunction "1_1") (pintype "bidirectional"))
      (node (ref "PHD47") (pin "1") (pinfunction "1_1") (pintype "bidirectional"))
      (node (ref "PHD48") (pin "1") (pinfunction "1_1") (pintype "bidirectional"))
      (node (ref "PHD49") (pin "1") (pinfunction "1_1") (pintype "bidirectional"))
      (node (ref "PHD5") (pin "1") (pinfunction "1_1") (pintype "bidirectional"))
      (node (ref "PHD50") (pin "1") (pinfunction "1_1") (pintype "bidirectional"))
      (node (ref "PHD51") (pin "1") (pinfunction "1_1") (pintype "bidirectional"))
      (node (ref "PHD52") (pin "1") (pinfunction "1_1") (pintype "bidirectional"))
      (node (ref "PHD53") (pin "1") (pinfunction "1_1") (pintype "bidirectional"))
      (node (ref "PHD54") (pin "1") (pinfunction "1_1") (pintype "bidirectional"))
      (node (ref "PHD55") (pin "1") (pinfunction "1_1") (pintype "bidirectional"))
      (node (ref "PHD56") (pin "1") (pinfunction "1_1") (pintype "bidirectional"))
      (node (ref "PHD57") (pin "1") (pinfunction "1_1") (pintype "bidirectional"))
      (node (ref "PHD58") (pin "1") (pinfunction "1_1") (pintype "bidirectional"))
      (node (ref "PHD59") (pin "1") (pinfunction "1_1") (pintype "bidirectional"))
      (node (ref "PHD6") (pin "1") (pinfunction "1_1") (pintype "bidirectional"))
      (node (ref "PHD60") (pin "1") (pinfunction "1_1") (pintype "bidirectional"))
      (node (ref "PHD61") (pin "1") (pinfunction "1_1") (pintype "bidirectional"))
      (node (ref "PHD62") (pin "1") (pinfunction "1_1") (pintype "bidirectional"))
      (node (ref "PHD63") (pin "1") (pinfunction "1_1") (pintype "bidirectional"))
      (node (ref "PHD64") (pin "1") (pinfunction "1_1") (pintype "bidirectional"))
      (node (ref "PHD65") (pin "1") (pinfunction "1_1") (pintype "bidirectional"))
      (node (ref "PHD66") (pin "1") (pinfunction "1_1") (pintype "bidirectional"))
      (node (ref "PHD67") (pin "1") (pinfunction "1_1") (pintype "bidirectional"))
      (node (ref "PHD68") (pin "1") (pinfunction "1_1") (pintype "bidirectional"))
      (node (ref "PHD69") (pin "1") (pinfunction "1_1") (pintype "bidirectional"))
      (node (ref "PHD7") (pin "1") (pinfunction "1_1") (pintype "bidirectional"))
      (node (ref "PHD70") (pin "1") (pinfunction "1_1") (pintype "bidirectional"))
      (node (ref "PHD71") (pin "1") (pinfunction "1_1") (pintype "bidirectional"))
      (node (ref "PHD72") (pin "1") (pinfunction "1_1") (pintype "bidirectional"))
      (node (ref "PHD73") (pin "1") (pinfunction "1_1") (pintype "bidirectional"))
      (node (ref "PHD74") (pin "1") (pinfunction "1_1") (pintype "bidirectional"))
      (node (ref "PHD75") (pin "1") (pinfunction "1_1") (pintype "bidirectional"))
      (node (ref "PHD76") (pin "1") (pinfunction "1_1") (pintype "bidirectional"))
      (node (ref "PHD77") (pin "1") (pinfunction "1_1") (pintype "bidirectional"))
      (node (ref "PHD78") (pin "1") (pinfunction "1_1") (pintype "bidirectional"))
      (node (ref "PHD79") (pin "1") (pinfunction "1_1") (pintype "bidirectional"))
      (node (ref "PHD8") (pin "1") (pinfunction "1_1") (pintype "bidirectional"))
      (node (ref "PHD80") (pin "1") (pinfunction "1_1") (pintype "bidirectional"))
      (node (ref "PHD81") (pin "1") (pinfunction "1_1") (pintype "bidirectional"))
      (node (ref "PHD82") (pin "1") (pinfunction "1_1") (pintype "bidirectional"))
      (node (ref "PHD83") (pin "1") (pinfunction "1_1") (pintype "bidirectional"))
      (node (ref "PHD84") (pin "1") (pinfunction "1_1") (pintype "bidirectional"))
      (node (ref "PHD85") (pin "1") (pinfunction "1_1") (pintype "bidirectional"))
      (node (ref "PHD86") (pin "1") (pinfunction "1_1") (pintype "bidirectional"))
      (node (ref "PHD87") (pin "1") (pinfunction "1_1") (pintype "bidirectional"))
      (node (ref "PHD88") (pin "1") (pinfunction "1_1") (pintype "bidirectional"))
      (node (ref "PHD89") (pin "1") (pinfunction "1_1") (pintype "bidirectional"))
      (node (ref "PHD9") (pin "1") (pinfunction "1_1") (pintype "bidirectional"))
      (node (ref "PHD90") (pin "1") (pinfunction "1_1") (pintype "bidirectional"))
      (node (ref "PHD91") (pin "1") (pinfunction "1_1") (pintype "bidirectional"))
      (node (ref "PHD92") (pin "1") (pinfunction "1_1") (pintype "bidirectional"))
      (node (ref "PHD93") (pin "1") (pinfunction "1_1") (pintype "bidirectional"))
      (node (ref "PHD94") (pin "1") (pinfunction "1_1") (pintype "bidirectional"))
      (node (ref "PHD95") (pin "1") (pinfunction "1_1") (pintype "bidirectional"))
      (node (ref "PHD96") (pin "1") (pinfunction "1_1") (pintype "bidirectional"))
      (node (ref "U1") (pin "12") (pinfunction "GND_12") (pintype "bidirectional"))
      (node (ref "U1") (pin "15") (pinfunction "EN_15") (pintype "bidirectional"))
      (node (ref "U2") (pin "12") (pinfunction "GND_12") (pintype "bidirectional"))
      (node (ref "U2") (pin "15") (pinfunction "EN_15") (pintype "bidirectional"))
      (node (ref "U3") (pin "12") (pinfunction "GND_12") (pintype "bidirectional"))
      (node (ref "U3") (pin "15") (pinfunction "EN_15") (pintype "bidirectional"))
      (node (ref "U4") (pin "12") (pinfunction "GND_12") (pintype "bidirectional"))
      (node (ref "U4") (pin "15") (pinfunction "EN_15") (pintype "bidirectional"))
      (node (ref "U5") (pin "12") (pinfunction "GND_12") (pintype "bidirectional"))
      (node (ref "U5") (pin "15") (pinfunction "EN_15") (pintype "bidirectional"))
      (node (ref "U6") (pin "12") (pinfunction "GND_12") (pintype "bidirectional"))
      (node (ref "U6") (pin "15") (pinfunction "EN_15") (pintype "bidirectional"))
    )
  )
)
